# Easy_RFPA_RevA_S1.net
KiCad netlist of a schematic drawn in EAGLE
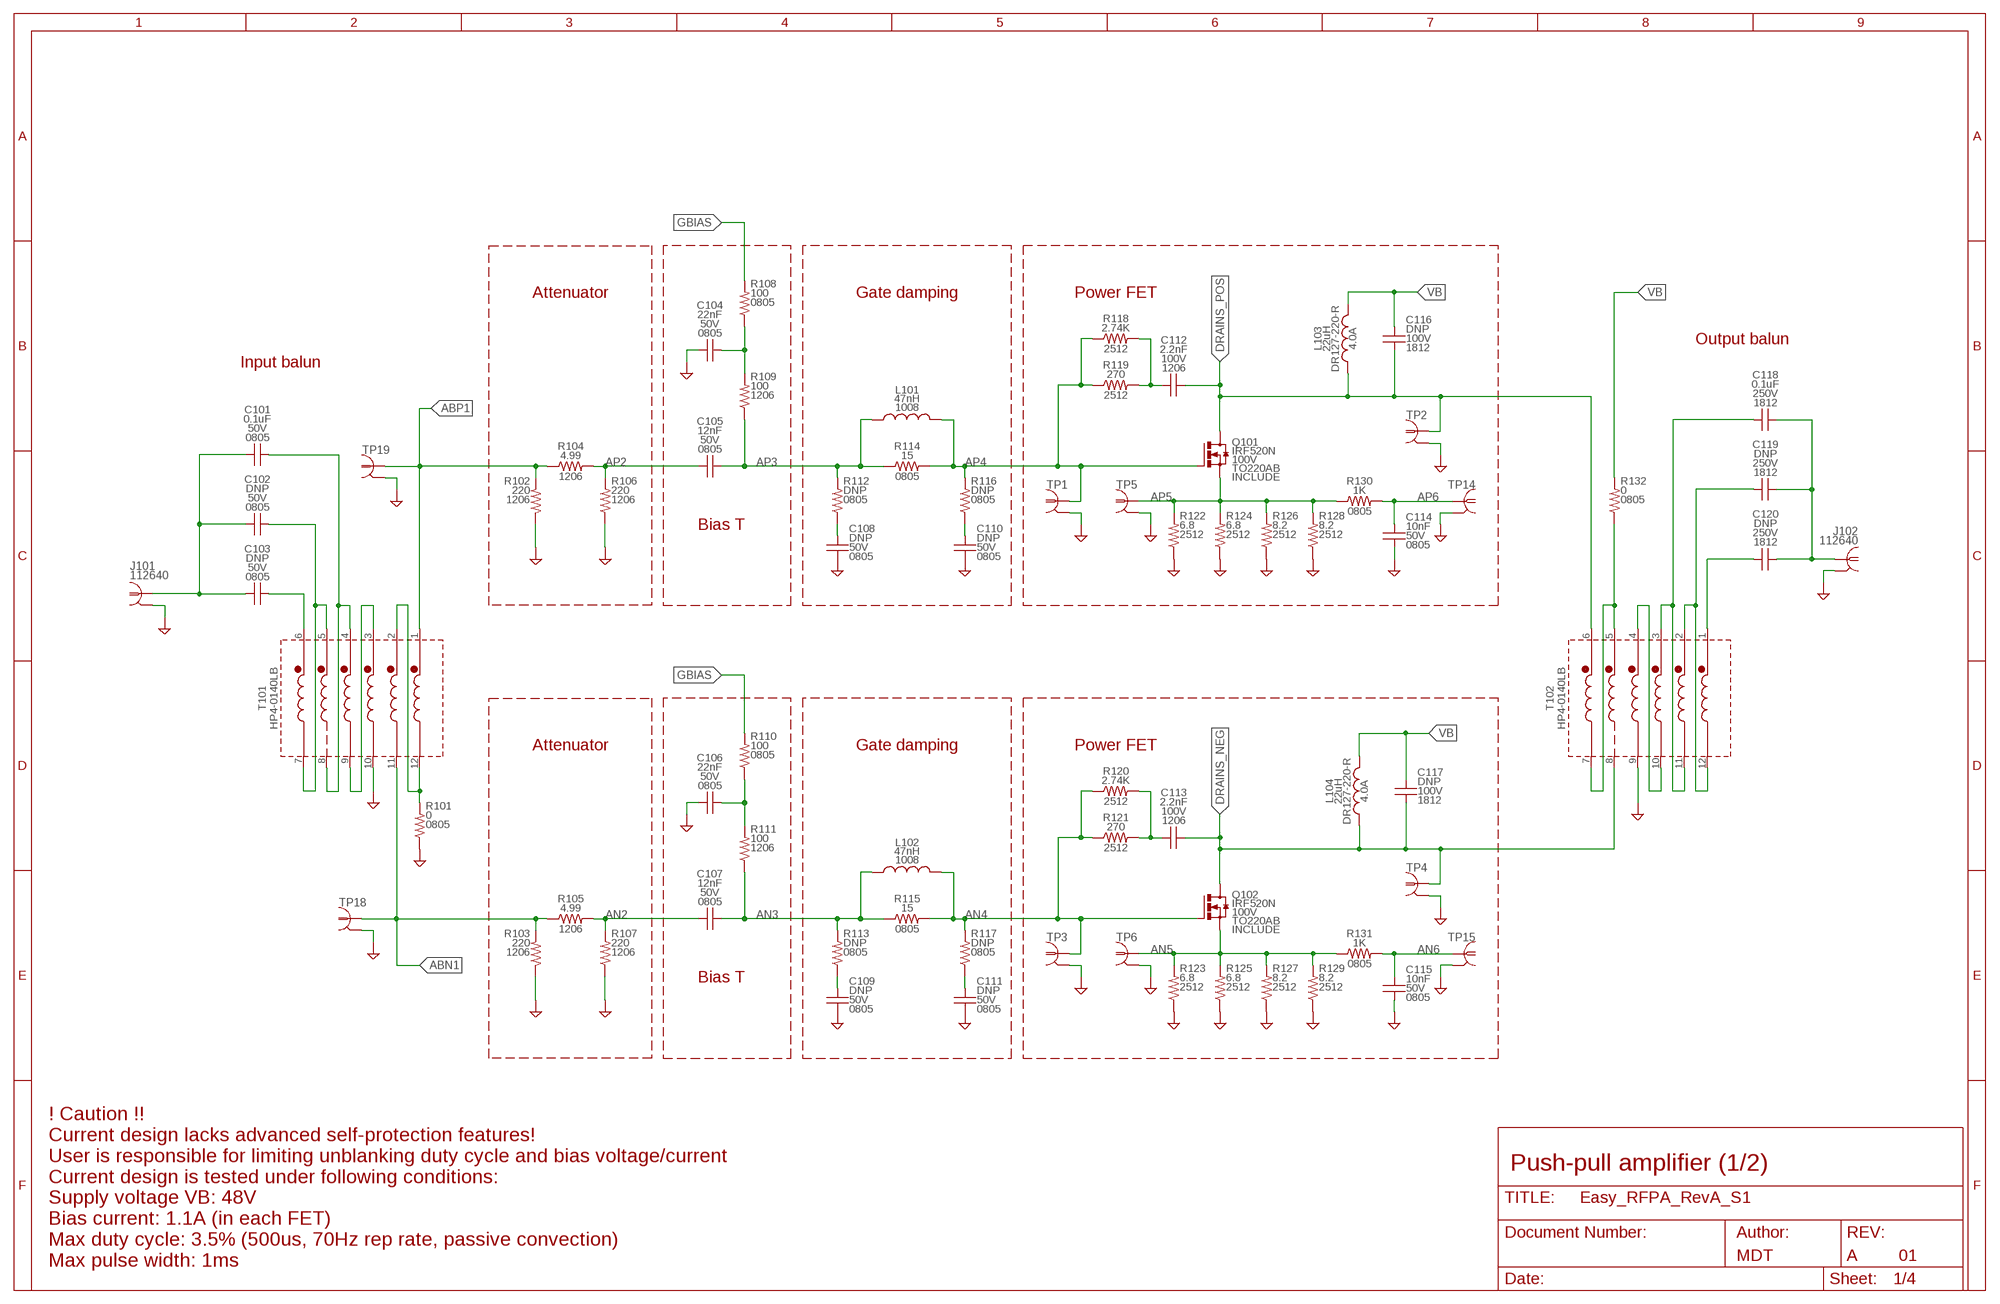
[diagram p0: schematic, sheet 1]
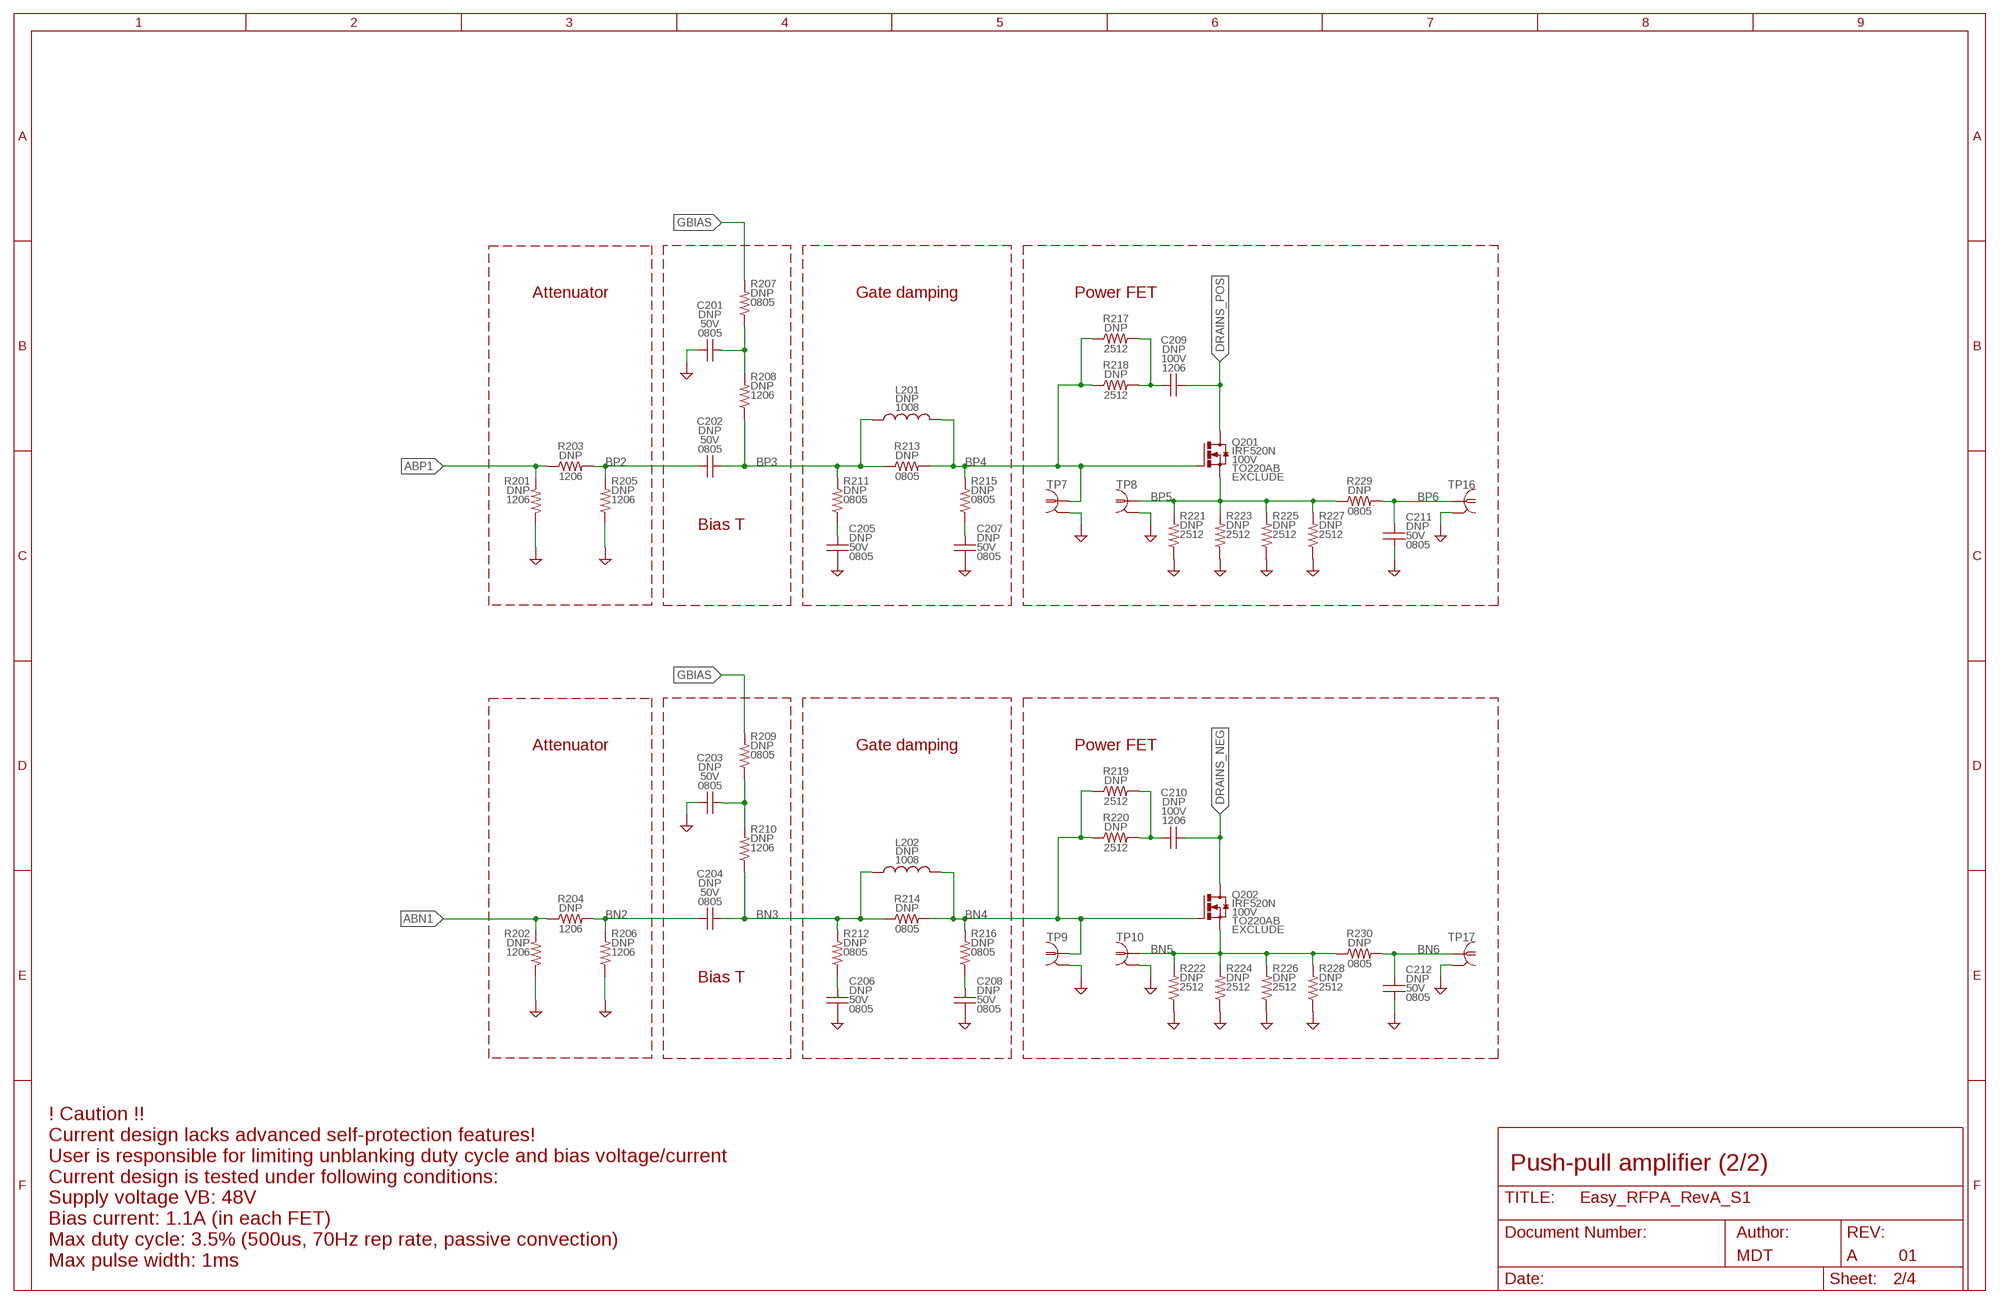
[diagram p1: schematic, sheet 2]
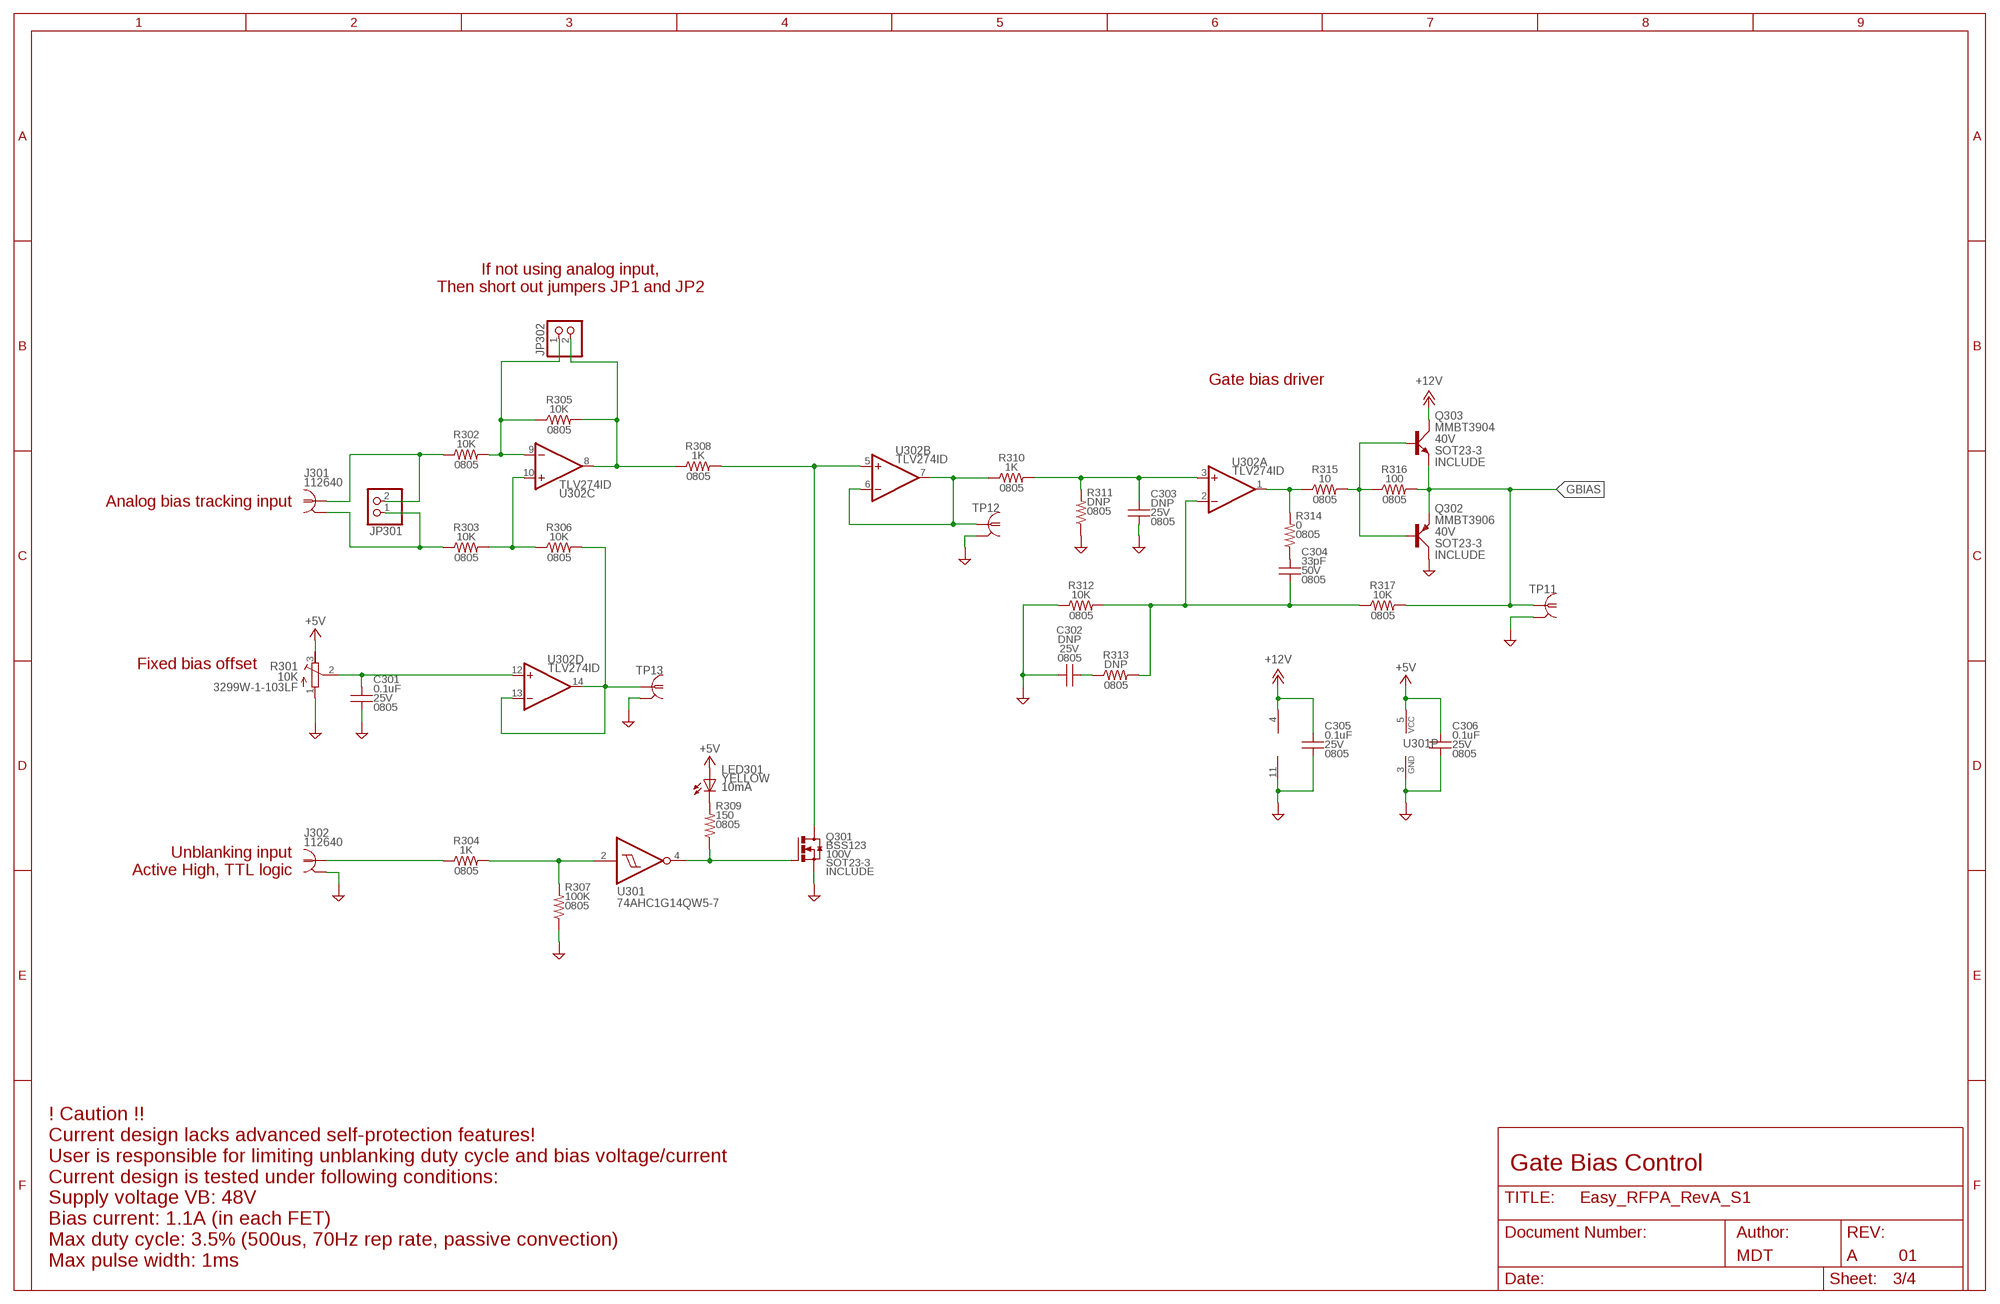
[diagram p2: schematic, sheet 3]
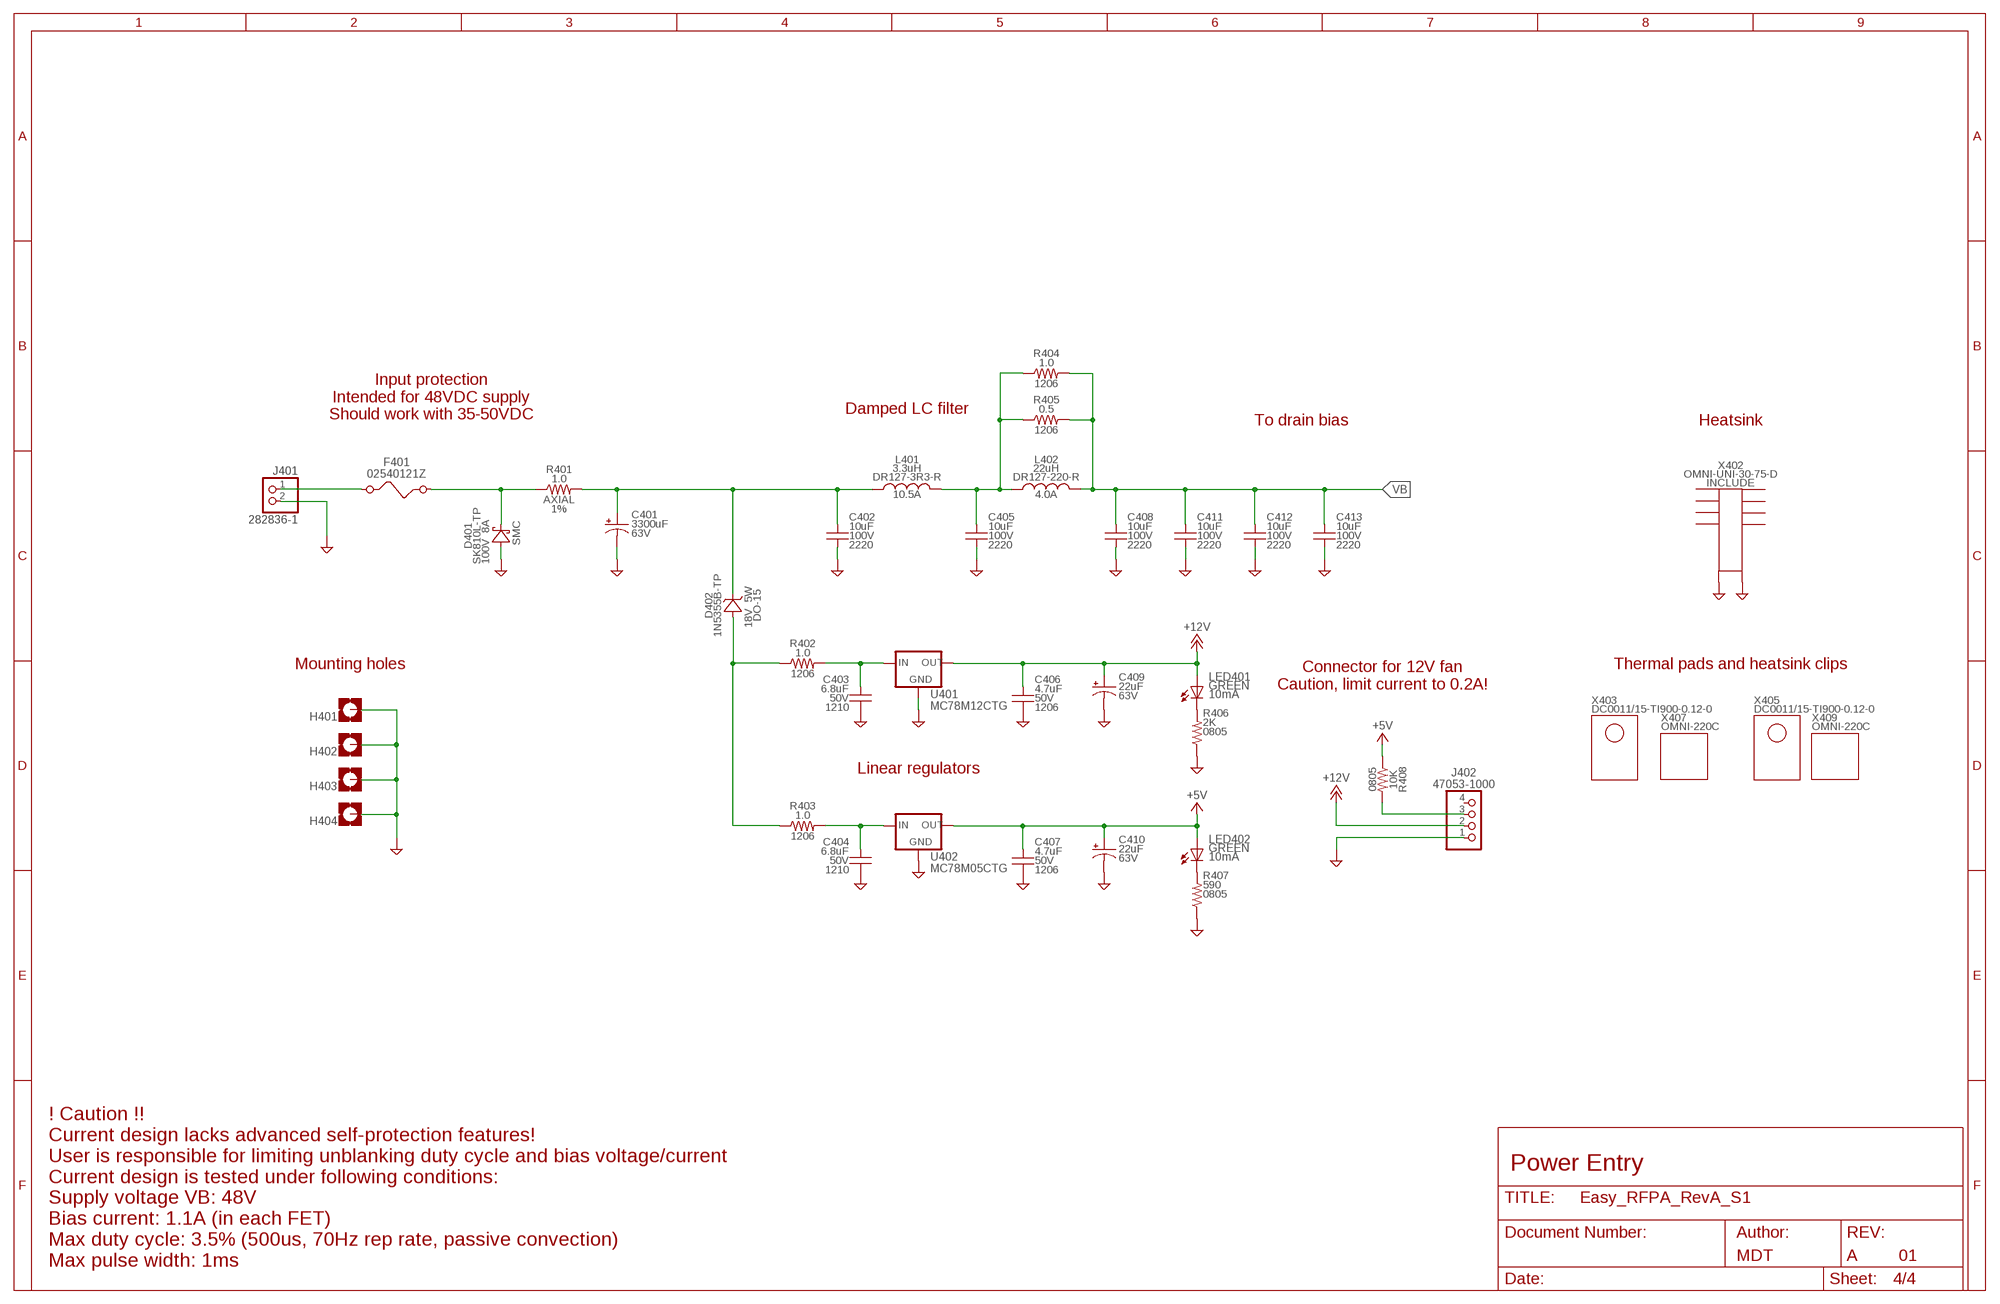
[diagram p3: schematic, sheet 4]

(export (version "E")
  (design (tool "Eeschema 10.0.6"))
  (components
    (comp (ref "C201")
      (value "DNP")
      (footprint "eagle-import:0805_IPC-7351B")
      (fields (field (name "PACKAGE") "0805") (field (name "BOM") "EXCLUDE") (field (name "VOLTAGE") "50V"))
      (libsource (lib "eagle-import") (part "C0805_IPCGEN"))
    )
    (comp (ref "C202")
      (value "DNP")
      (footprint "eagle-import:0805_IPC-7351B")
      (fields (field (name "PACKAGE") "0805") (field (name "BOM") "EXCLUDE") (field (name "VOLTAGE") "50V"))
      (libsource (lib "eagle-import") (part "C0805_IPCGEN"))
    )
    (comp (ref "C203")
      (value "DNP")
      (footprint "eagle-import:0805_IPC-7351B")
      (fields (field (name "PACKAGE") "0805") (field (name "BOM") "EXCLUDE") (field (name "VOLTAGE") "50V"))
      (libsource (lib "eagle-import") (part "C0805_IPCGEN"))
    )
    (comp (ref "C204")
      (value "DNP")
      (footprint "eagle-import:0805_IPC-7351B")
      (fields (field (name "PACKAGE") "0805") (field (name "BOM") "EXCLUDE") (field (name "VOLTAGE") "50V"))
      (libsource (lib "eagle-import") (part "C0805_IPCGEN"))
    )
    (comp (ref "C205")
      (value "DNP")
      (footprint "eagle-import:0805_IPC-7351B")
      (fields (field (name "BOM") "EXCLUDE") (field (name "VOLTAGE") "50V"))
      (libsource (lib "eagle-import") (part "C0805_IPCGEN"))
    )
    (comp (ref "C206")
      (value "DNP")
      (footprint "eagle-import:0805_IPC-7351B")
      (fields (field (name "BOM") "EXCLUDE") (field (name "VOLTAGE") "50V"))
      (libsource (lib "eagle-import") (part "C0805_IPCGEN"))
    )
    (comp (ref "C207")
      (value "DNP")
      (footprint "eagle-import:0805_IPC-7351B")
      (fields (field (name "BOM") "EXCLUDE") (field (name "VOLTAGE") "50V"))
      (libsource (lib "eagle-import") (part "C0805_IPCGEN"))
    )
    (comp (ref "C208")
      (value "DNP")
      (footprint "eagle-import:0805_IPC-7351B")
      (fields (field (name "BOM") "EXCLUDE") (field (name "VOLTAGE") "50V"))
      (libsource (lib "eagle-import") (part "C0805_IPCGEN"))
    )
    (comp (ref "C209")
      (value "DNP")
      (footprint "eagle-import:C1206")
      (fields (field (name "PACKAGE") "1206") (field (name "BOM") "EXCLUDE") (field (name "VOLTAGE") "100V"))
      (libsource (lib "eagle-import") (part "CC1206GEN"))
    )
    (comp (ref "C210")
      (value "DNP")
      (footprint "eagle-import:C1206")
      (fields (field (name "PACKAGE") "1206") (field (name "BOM") "EXCLUDE") (field (name "VOLTAGE") "100V"))
      (libsource (lib "eagle-import") (part "CC1206GEN"))
    )
    (comp (ref "C211")
      (value "DNP")
      (footprint "eagle-import:0805_IPC-7351B")
      (fields (field (name "BOM") "EXCLUDE") (field (name "VOLTAGE") "50V"))
      (libsource (lib "eagle-import") (part "C0805_IPCGEN"))
    )
    (comp (ref "C212")
      (value "DNP")
      (footprint "eagle-import:0805_IPC-7351B")
      (fields (field (name "BOM") "EXCLUDE") (field (name "VOLTAGE") "50V"))
      (libsource (lib "eagle-import") (part "C0805_IPCGEN"))
    )
    (comp (ref "L201")
      (value "DNP")
      (footprint "eagle-import:L1008")
      (fields (field (name "PARTNO") "1008CS-470XJLC") (field (name "BOM") "EXCLUDE"))
      (libsource (lib "eagle-import") (part "L_CHIP1008L-47N-AIR-5%-1008-1A"))
    )
    (comp (ref "L202")
      (value "DNP")
      (footprint "eagle-import:L1008")
      (fields (field (name "PARTNO") "1008CS-470XJLC") (field (name "BOM") "EXCLUDE"))
      (libsource (lib "eagle-import") (part "L_CHIP1008L-47N-AIR-5%-1008-1A"))
    )
    (comp (ref "Q201")
      (value "IRF630")
      (footprint "eagle-import:TO220BV")
      (fields
        (field (name "PARTNO") "IRF520NPBF")
        (field (name "VOLTAGE") "100V")
        (field (name "BOM") "EXCLUDE")
      )
      (libsource (lib "eagle-import") (part "MOSFET_NTO-220-VERTIRF520N"))
    )
    (comp (ref "Q202")
      (value "IRF630")
      (footprint "eagle-import:TO220BV")
      (fields
        (field (name "PARTNO") "IRF520NPBF")
        (field (name "VOLTAGE") "100V")
        (field (name "BOM") "EXCLUDE")
      )
      (libsource (lib "eagle-import") (part "MOSFET_NTO-220-VERTIRF520N"))
    )
    (comp (ref "R201")
      (value "DNP")
      (footprint "eagle-import:1206_IPC-7351B")
      (fields (field (name "BOM") "EXCLUDE"))
      (libsource (lib "eagle-import") (part "R1206_IPCGEN"))
    )
    (comp (ref "R202")
      (value "DNP")
      (footprint "eagle-import:1206_IPC-7351B")
      (fields (field (name "BOM") "EXCLUDE"))
      (libsource (lib "eagle-import") (part "R1206_IPCGEN"))
    )
    (comp (ref "R203")
      (value "DNP")
      (footprint "eagle-import:1206_IPC-7351B")
      (fields (field (name "BOM") "EXCLUDE"))
      (libsource (lib "eagle-import") (part "R901206_IPCGEN"))
    )
    (comp (ref "R204")
      (value "DNP")
      (footprint "eagle-import:1206_IPC-7351B")
      (fields (field (name "BOM") "EXCLUDE"))
      (libsource (lib "eagle-import") (part "R901206_IPCGEN"))
    )
    (comp (ref "R205")
      (value "DNP")
      (footprint "eagle-import:1206_IPC-7351B")
      (fields (field (name "BOM") "EXCLUDE"))
      (libsource (lib "eagle-import") (part "R1206_IPCGEN"))
    )
    (comp (ref "R206")
      (value "DNP")
      (footprint "eagle-import:1206_IPC-7351B")
      (fields (field (name "BOM") "EXCLUDE"))
      (libsource (lib "eagle-import") (part "R1206_IPCGEN"))
    )
    (comp (ref "R207")
      (value "DNP")
      (footprint "eagle-import:0805_IPC-7351B")
      (fields (field (name "BOM") "EXCLUDE"))
      (libsource (lib "eagle-import") (part "R0805_IPCGEN"))
    )
    (comp (ref "R208")
      (value "DNP")
      (footprint "eagle-import:1206_IPC-7351B")
      (fields (field (name "BOM") "EXCLUDE"))
      (libsource (lib "eagle-import") (part "R1206_IPCGEN"))
    )
    (comp (ref "R209")
      (value "DNP")
      (footprint "eagle-import:0805_IPC-7351B")
      (fields (field (name "BOM") "EXCLUDE"))
      (libsource (lib "eagle-import") (part "R0805_IPCGEN"))
    )
    (comp (ref "R210")
      (value "DNP")
      (footprint "eagle-import:1206_IPC-7351B")
      (fields (field (name "BOM") "EXCLUDE"))
      (libsource (lib "eagle-import") (part "R1206_IPCGEN"))
    )
    (comp (ref "R211")
      (value "DNP")
      (footprint "eagle-import:0805_IPC-7351B")
      (fields (field (name "BOM") "EXCLUDE"))
      (libsource (lib "eagle-import") (part "R0805_IPCGEN"))
    )
    (comp (ref "R212")
      (value "DNP")
      (footprint "eagle-import:0805_IPC-7351B")
      (fields (field (name "BOM") "EXCLUDE"))
      (libsource (lib "eagle-import") (part "R0805_IPCGEN"))
    )
    (comp (ref "R213")
      (value "DNP")
      (footprint "eagle-import:0805_IPC-7351B")
      (fields (field (name "BOM") "EXCLUDE"))
      (libsource (lib "eagle-import") (part "R900805_IPCGEN"))
    )
    (comp (ref "R214")
      (value "DNP")
      (footprint "eagle-import:0805_IPC-7351B")
      (fields (field (name "BOM") "EXCLUDE"))
      (libsource (lib "eagle-import") (part "R900805_IPCGEN"))
    )
    (comp (ref "R215")
      (value "DNP")
      (footprint "eagle-import:0805_IPC-7351B")
      (fields (field (name "BOM") "EXCLUDE"))
      (libsource (lib "eagle-import") (part "R0805_IPCGEN"))
    )
    (comp (ref "R216")
      (value "DNP")
      (footprint "eagle-import:0805_IPC-7351B")
      (fields (field (name "BOM") "EXCLUDE"))
      (libsource (lib "eagle-import") (part "R0805_IPCGEN"))
    )
    (comp (ref "R217")
      (value "DNP")
      (footprint "eagle-import:R2512")
      (fields (field (name "BOM") "EXCLUDE"))
      (libsource (lib "eagle-import") (part "R90R2512GEN"))
    )
    (comp (ref "R218")
      (value "DNP")
      (footprint "eagle-import:R2512")
      (fields (field (name "BOM") "EXCLUDE"))
      (libsource (lib "eagle-import") (part "R90R2512GEN"))
    )
    (comp (ref "R219")
      (value "DNP")
      (footprint "eagle-import:R2512")
      (fields (field (name "BOM") "EXCLUDE"))
      (libsource (lib "eagle-import") (part "R90R2512GEN"))
    )
    (comp (ref "R220")
      (value "DNP")
      (footprint "eagle-import:R2512")
      (fields (field (name "BOM") "EXCLUDE"))
      (libsource (lib "eagle-import") (part "R90R2512GEN"))
    )
    (comp (ref "R221")
      (value "DNP")
      (footprint "eagle-import:R2512")
      (fields (field (name "BOM") "EXCLUDE"))
      (libsource (lib "eagle-import") (part "RR2512GEN"))
    )
    (comp (ref "R222")
      (value "DNP")
      (footprint "eagle-import:R2512")
      (fields (field (name "BOM") "EXCLUDE"))
      (libsource (lib "eagle-import") (part "RR2512GEN"))
    )
    (comp (ref "R223")
      (value "DNP")
      (footprint "eagle-import:R2512")
      (fields (field (name "BOM") "EXCLUDE"))
      (libsource (lib "eagle-import") (part "RR2512GEN"))
    )
    (comp (ref "R224")
      (value "DNP")
      (footprint "eagle-import:R2512")
      (fields (field (name "BOM") "EXCLUDE"))
      (libsource (lib "eagle-import") (part "RR2512GEN"))
    )
    (comp (ref "R225")
      (value "DNP")
      (footprint "eagle-import:R2512")
      (fields (field (name "BOM") "EXCLUDE"))
      (libsource (lib "eagle-import") (part "RR2512GEN"))
    )
    (comp (ref "R226")
      (value "DNP")
      (footprint "eagle-import:R2512")
      (fields (field (name "BOM") "EXCLUDE"))
      (libsource (lib "eagle-import") (part "RR2512GEN"))
    )
    (comp (ref "R227")
      (value "DNP")
      (footprint "eagle-import:R2512")
      (fields (field (name "BOM") "EXCLUDE"))
      (libsource (lib "eagle-import") (part "RR2512GEN"))
    )
    (comp (ref "R228")
      (value "DNP")
      (footprint "eagle-import:R2512")
      (fields (field (name "BOM") "EXCLUDE"))
      (libsource (lib "eagle-import") (part "RR2512GEN"))
    )
    (comp (ref "R229")
      (value "DNP")
      (footprint "eagle-import:0805_IPC-7351B")
      (fields (field (name "BOM") "EXCLUDE"))
      (libsource (lib "eagle-import") (part "R900805_IPCGEN"))
    )
    (comp (ref "R230")
      (value "DNP")
      (footprint "eagle-import:0805_IPC-7351B")
      (fields (field (name "BOM") "EXCLUDE"))
      (libsource (lib "eagle-import") (part "R900805_IPCGEN"))
    )
    (comp (ref "TP7")
      (value "PROBE_TPTP_5MM")
      (footprint "eagle-import:PROBE_TP_5MM")
      (libsource (lib "eagle-import") (part "PROBE_TPTP_5MM"))
    )
    (comp (ref "TP8")
      (value "PROBE_TPTP_7P5MM")
      (footprint "eagle-import:PROBE_TP_7P5MM")
      (libsource (lib "eagle-import") (part "PROBE_TPTP_7P5MM"))
    )
    (comp (ref "TP9")
      (value "PROBE_TPTP_5MM")
      (footprint "eagle-import:PROBE_TP_5MM")
      (libsource (lib "eagle-import") (part "PROBE_TPTP_5MM"))
    )
    (comp (ref "TP10")
      (value "PROBE_TPTP_5MM")
      (footprint "eagle-import:PROBE_TP_5MM")
      (libsource (lib "eagle-import") (part "PROBE_TPTP_5MM"))
    )
    (comp (ref "TP16")
      (value "PROBE_TPTP_5MM")
      (footprint "eagle-import:PROBE_TP_5MM")
      (libsource (lib "eagle-import") (part "PROBE_TPTP_5MM"))
    )
    (comp (ref "TP17")
      (value "PROBE_TPTP_7P5MM")
      (footprint "eagle-import:PROBE_TP_7P5MM")
      (libsource (lib "eagle-import") (part "PROBE_TPTP_7P5MM"))
    )
    (comp (ref "C401")
      (value "3300uF")
      (footprint "eagle-import:EB25D")
      (fields (field (name "PARTNO") "MAL225638332E3") (field (name "VOLTAGE") "63V"))
      (libsource (lib "eagle-import") (part "CPOLEB25DC-3300U-63V-20%-25DX37L-ELEC"))
    )
    (comp (ref "C402")
      (value "10uF")
      (footprint "eagle-import:C2220_CKG57N")
      (fields
        (field (name "BOM") "INCLUDE")
        (field (name "PACKAGE") "2220")
        (field (name "PARTNO") "CGA9N3X7S2A106M230KE")
        (field (name "VOLTAGE") "100V")
      )
      (libsource (lib "eagle-import") (part "CC2220_CKG57NCC-10U-100V-20%-2220-X7T"))
    )
    (comp (ref "C403")
      (value "6.8uF")
      (footprint "eagle-import:C1210")
      (fields (field (name "DIALECTRIC") "X7S") (field (name "VOLTAGE") "50V"))
      (libsource (lib "eagle-import") (part "CC1210GEN"))
    )
    (comp (ref "C404")
      (value "6.8uF")
      (footprint "eagle-import:C1210")
      (fields (field (name "DIALECTRIC") "X7S") (field (name "VOLTAGE") "50V"))
      (libsource (lib "eagle-import") (part "CC1210GEN"))
    )
    (comp (ref "C405")
      (value "10uF")
      (footprint "eagle-import:C2220_CKG57N")
      (fields
        (field (name "BOM") "INCLUDE")
        (field (name "PACKAGE") "2220")
        (field (name "PARTNO") "CGA9N3X7S2A106M230KE")
        (field (name "VOLTAGE") "100V")
      )
      (libsource (lib "eagle-import") (part "CC2220_CKG57NCC-10U-100V-20%-2220-X7T"))
    )
    (comp (ref "C406")
      (value "4.7uF")
      (footprint "eagle-import:C1206")
      (fields (field (name "DIALECTRIC") "X7R") (field (name "VOLTAGE") "50V"))
      (libsource (lib "eagle-import") (part "CC1206GEN"))
    )
    (comp (ref "C407")
      (value "4.7uF")
      (footprint "eagle-import:C1206")
      (fields (field (name "DIALECTRIC") "X7R") (field (name "VOLTAGE") "50V"))
      (libsource (lib "eagle-import") (part "CC1206GEN"))
    )
    (comp (ref "C408")
      (value "10uF")
      (footprint "eagle-import:C2220_CKG57N")
      (fields (field (name "PARTNO") "CGA9N3X7S2A106M230KE") (field (name "VOLTAGE") "100V"))
      (libsource (lib "eagle-import") (part "CC2220_CKG57NCC-10U-100V-20%-2220-X7T"))
    )
    (comp (ref "C409")
      (value "22uF")
      (footprint "eagle-import:E2,5-7")
      (fields (field (name "PARTNO") "860010773010") (field (name "VOLTAGE") "63V"))
      (libsource (lib "eagle-import") (part "CPOLE2,5-7C-22U-63V-20%-6.3DX12.5L-ELEC"))
    )
    (comp (ref "C410")
      (value "22uF")
      (footprint "eagle-import:E2,5-7")
      (fields (field (name "PARTNO") "860010773010") (field (name "VOLTAGE") "63V"))
      (libsource (lib "eagle-import") (part "CPOLE2,5-7C-22U-63V-20%-6.3DX12.5L-ELEC"))
    )
    (comp (ref "C411")
      (value "10uF")
      (footprint "eagle-import:C2220_CKG57N")
      (fields (field (name "PARTNO") "CGA9N3X7S2A106M230KE") (field (name "VOLTAGE") "100V"))
      (libsource (lib "eagle-import") (part "CC2220_CKG57NCC-10U-100V-20%-2220-X7T"))
    )
    (comp (ref "C412")
      (value "10uF")
      (footprint "eagle-import:C2220_CKG57N")
      (fields (field (name "PARTNO") "CGA9N3X7S2A106M230KE") (field (name "VOLTAGE") "100V"))
      (libsource (lib "eagle-import") (part "CC2220_CKG57NCC-10U-100V-20%-2220-X7T"))
    )
    (comp (ref "C413")
      (value "10uF")
      (footprint "eagle-import:C2220_CKG57N")
      (fields (field (name "PARTNO") "CGA9N3X7S2A106M230KE") (field (name "VOLTAGE") "100V"))
      (libsource (lib "eagle-import") (part "CC2220_CKG57NCC-10U-100V-20%-2220-X7T"))
    )
    (comp (ref "D401")
      (value "D-SCHOTTKYSK810L-TPSMC")
      (footprint "eagle-import:DO-214AB(SMC)")
      (fields (field (name "PARTNO") "SK810L-TP") (field (name "VOLTAGE") "100V"))
      (libsource (lib "eagle-import") (part "D-SCHOTTKYSMCSK810L-TP"))
    )
    (comp (ref "D402")
      (value "D-ZENER1N5355B-TPDO15-12")
      (footprint "eagle-import:DO15-12")
      (fields (field (name "PARTNO") "1N5355B-TP") (field (name "POWER") "5W") (field (name "VOLTAGE") "18V"))
      (libsource (lib "eagle-import") (part "D-ZENERDO15-121N5355B-TP"))
    )
    (comp (ref "F401")
      (value "FUSE_2P")
      (footprint "eagle-import:02540121Z")
      (fields (field (name "PARTNO") "02540121Z"))
      (libsource (lib "eagle-import") (part "FUSE_2P"))
    )
    (comp (ref "H401")
      (value "MOUNT-PAD-SQUARE3.2")
      (footprint "eagle-import:3,2-PAD-SQUARE")
      (libsource (lib "eagle-import") (part "MOUNT-PAD-SQUARE3.2"))
    )
    (comp (ref "H402")
      (value "MOUNT-PAD-SQUARE3.2")
      (footprint "eagle-import:3,2-PAD-SQUARE")
      (libsource (lib "eagle-import") (part "MOUNT-PAD-SQUARE3.2"))
    )
    (comp (ref "H403")
      (value "MOUNT-PAD-SQUARE3.2")
      (footprint "eagle-import:3,2-PAD-SQUARE")
      (libsource (lib "eagle-import") (part "MOUNT-PAD-SQUARE3.2"))
    )
    (comp (ref "H404")
      (value "MOUNT-PAD-SQUARE3.2")
      (footprint "eagle-import:3,2-PAD-SQUARE")
      (libsource (lib "eagle-import") (part "MOUNT-PAD-SQUARE3.2"))
    )
    (comp (ref "J401")
      (value "HDR_2X1282836-1282836-1")
      (footprint "eagle-import:W237-02")
      (fields (field (name "PARTNO") "282836-1"))
      (libsource (lib "eagle-import") (part "HDR_2X1282836-1282836-1"))
    )
    (comp (ref "J402")
      (value "KK_PCFAN")
      (footprint "eagle-import:47053-1000")
      (fields (field (name "PARTNO") "47053-1000"))
      (libsource (lib "eagle-import") (part "KK_PCFAN"))
    )
    (comp (ref "L401")
      (value "3.3uH")
      (footprint "eagle-import:DR127")
      (fields (field (name "PARTNO") "DR127-3R3-R"))
      (libsource (lib "eagle-import") (part "LL-3.3U-FERRITE-20%-12.5X12.5MM-10.5A"))
    )
    (comp (ref "L402")
      (value "22uH")
      (footprint "eagle-import:DR127")
      (fields (field (name "PARTNO") "DR127-220-R"))
      (libsource (lib "eagle-import") (part "LL-22U-FERRITE-20%-12.5X12.5MM-4A"))
    )
    (comp (ref "LED401")
      (value "LEDHLMP-3962-F0002T1_3/4")
      (footprint "eagle-import:LED5MM")
      (fields (field (name "PARTNO") "HLMP-3962-F0002"))
      (libsource (lib "eagle-import") (part "LEDT1_3/4HLMP-3962-F0002"))
    )
    (comp (ref "LED402")
      (value "LEDHLMP-3962-F0002T1_3/4")
      (footprint "eagle-import:LED5MM")
      (fields (field (name "PARTNO") "HLMP-3962-F0002"))
      (libsource (lib "eagle-import") (part "LEDT1_3/4HLMP-3962-F0002"))
    )
    (comp (ref "R401")
      (value "1.0")
      (footprint "eagle-import:P0817V")
      (fields (field (name "PARTNO") "PAC300001008FAC000") (field (name "POWER") "3W"))
      (libsource (lib "eagle-import") (part "R90P0817VR-1.0-1%-AXIAL-3W"))
    )
    (comp (ref "R402")
      (value "1.0")
      (footprint "eagle-import:R1206")
      (libsource (lib "eagle-import") (part "R90R1206GEN"))
    )
    (comp (ref "R403")
      (value "1.0")
      (footprint "eagle-import:R1206")
      (libsource (lib "eagle-import") (part "R90R1206GEN"))
    )
    (comp (ref "R404")
      (value "1.0")
      (footprint "eagle-import:1206_IPC-7351B")
      (libsource (lib "eagle-import") (part "R901206_IPCGEN"))
    )
    (comp (ref "R405")
      (value "0.5")
      (footprint "eagle-import:1206_IPC-7351B")
      (libsource (lib "eagle-import") (part "R901206_IPCGEN"))
    )
    (comp (ref "R406")
      (value "2K")
      (footprint "eagle-import:0805_IPC-7351B")
      (libsource (lib "eagle-import") (part "R0805_IPCGEN"))
    )
    (comp (ref "R407")
      (value "590")
      (footprint "eagle-import:0805_IPC-7351B")
      (libsource (lib "eagle-import") (part "R0805_IPCGEN"))
    )
    (comp (ref "R408")
      (value "10K")
      (footprint "eagle-import:0805_IPC-7351B")
      (libsource (lib "eagle-import") (part "R900805_IPCGEN"))
    )
    (comp (ref "U401")
      (value "LDO_3TERMMC78M12CTGTO220_VERT")
      (footprint "eagle-import:TO220BV")
      (fields (field (name "PARTNO") "MC78M12CTG"))
      (libsource (lib "eagle-import") (part "LDO_3TERMTO220_VERTMC78M12CTG"))
    )
    (comp (ref "U402")
      (value "LDO_3TERMMC78M05CTGTO220_VERT")
      (footprint "eagle-import:TO220BV")
      (fields (field (name "PARTNO") "MC78M05CTG"))
      (libsource (lib "eagle-import") (part "LDO_3TERMTO220_VERTMC78M05CTG"))
    )
    (comp (ref "X402")
      (value "HEATSINK_OMNI_DUALOMNI-UNI-30-75-D30-75-D")
      (footprint "eagle-import:OMNI-UNI-30-75-D")
      (fields (field (name "PARTNO") "OMNI-UNI-30-75-D"))
      (libsource (lib "eagle-import") (part "HEATSINK_OMNI_DUAL30-75-DOMNI-UNI-30-75-D"))
    )
    (comp (ref "C301")
      (value "0.1uF")
      (footprint "eagle-import:0805_IPC-7351B")
      (fields (field (name "VOLTAGE") "25V"))
      (libsource (lib "eagle-import") (part "C0805_IPCGEN"))
    )
    (comp (ref "C302")
      (value "DNP")
      (footprint "eagle-import:0805_IPC-7351B")
      (fields (field (name "PACKAGE") "0805") (field (name "BOM") "EXCLUDE") (field (name "VOLTAGE") "25V"))
      (libsource (lib "eagle-import") (part "C0805_IPCGEN"))
    )
    (comp (ref "C303")
      (value "DNP")
      (footprint "eagle-import:0805_IPC-7351B")
      (fields (field (name "BOM") "EXCLUDE") (field (name "VOLTAGE") "25V"))
      (libsource (lib "eagle-import") (part "C0805_IPCGEN"))
    )
    (comp (ref "C304")
      (value "33pF")
      (footprint "eagle-import:0805_IPC-7351B")
      (fields (field (name "VOLTAGE") "50V"))
      (libsource (lib "eagle-import") (part "C0805_IPCGEN"))
    )
    (comp (ref "C305")
      (value "0.1uF")
      (footprint "eagle-import:0805_IPC-7351B")
      (fields (field (name "VOLTAGE") "25V"))
      (libsource (lib "eagle-import") (part "C0805_IPCGEN"))
    )
    (comp (ref "C306")
      (value "0.1uF")
      (footprint "eagle-import:0805_IPC-7351B")
      (fields (field (name "VOLTAGE") "25V"))
      (libsource (lib "eagle-import") (part "C0805_IPCGEN"))
    )
    (comp (ref "J301")
      (value "COAX112640BNC_EDGE")
      (footprint "eagle-import:BNC_EDGE")
      (fields (field (name "PARTNO") "112640"))
      (libsource (lib "eagle-import") (part "COAXBNC_EDGE112640"))
    )
    (comp (ref "J302")
      (value "COAX112640BNC_EDGE")
      (footprint "eagle-import:BNC_EDGE")
      (fields (field (name "PARTNO") "112640"))
      (libsource (lib "eagle-import") (part "COAXBNC_EDGE112640"))
    )
    (comp (ref "JP301")
      (value "PINHD-1X2")
      (footprint "eagle-import:1X02")
      (libsource (lib "eagle-import") (part "PINHD-1X2"))
    )
    (comp (ref "JP302")
      (value "PINHD-1X2")
      (footprint "eagle-import:1X02")
      (libsource (lib "eagle-import") (part "PINHD-1X2"))
    )
    (comp (ref "LED301")
      (value "LEDHLMP-3401-E0002T1_3/4")
      (footprint "eagle-import:LED5MM")
      (fields (field (name "PARTNO") " HLMP-3401-E0002"))
      (libsource (lib "eagle-import") (part "LEDT1_3/4HLMP-3401-E0002"))
    )
    (comp (ref "Q301")
      (value "MOSFET_NBSS123SOT23")
      (footprint "eagle-import:SOT23R_INFINEON")
      (fields (field (name "PARTNO") "BSS123-7-F") (field (name "VOLTAGE") "100V"))
      (libsource (lib "eagle-import") (part "MOSFET_NSOT23BSS123"))
    )
    (comp (ref "Q302")
      (value "PNPSOT23_BEC")
      (footprint "eagle-import:SOT23R_INFINEON")
      (fields (field (name "VOLTAGE") "40V") (field (name "PARTNO") "PMBT3906,215"))
      (libsource (lib "eagle-import") (part "PNPSOT23_BEC"))
    )
    (comp (ref "Q303")
      (value "NPNMMBT3904SOT23_BEC")
      (footprint "eagle-import:SOT23R_INFINEON")
      (fields (field (name "PARTNO") "MMBT3904,215") (field (name "VOLTAGE") "40V"))
      (libsource (lib "eagle-import") (part "NPNSOT23_BECMMBT3904"))
    )
    (comp (ref "R301")
      (value "10K")
      (footprint "eagle-import:RTRIM3299W")
      (fields (field (name "PARTNO") "3299W-1-103LF") (field (name "POWER") "0.5W"))
      (libsource (lib "eagle-import") (part "RTRIM3299WRTRIM-10K-10%-3299W-0.5W"))
    )
    (comp (ref "R302")
      (value "10K")
      (footprint "eagle-import:0805_IPC-7351B")
      (libsource (lib "eagle-import") (part "R900805_IPCGEN"))
    )
    (comp (ref "R303")
      (value "10K")
      (footprint "eagle-import:0805_IPC-7351B")
      (libsource (lib "eagle-import") (part "R900805_IPCGEN"))
    )
    (comp (ref "R304")
      (value "1K")
      (footprint "eagle-import:0805_IPC-7351B")
      (libsource (lib "eagle-import") (part "R900805_IPCGEN"))
    )
    (comp (ref "R305")
      (value "10K")
      (footprint "eagle-import:0805_IPC-7351B")
      (libsource (lib "eagle-import") (part "R900805_IPCGEN"))
    )
    (comp (ref "R306")
      (value "10K")
      (footprint "eagle-import:0805_IPC-7351B")
      (libsource (lib "eagle-import") (part "R900805_IPCGEN"))
    )
    (comp (ref "R307")
      (value "100K")
      (footprint "eagle-import:0805_IPC-7351B")
      (libsource (lib "eagle-import") (part "R0805_IPCGEN"))
    )
    (comp (ref "R308")
      (value "1K")
      (footprint "eagle-import:0805_IPC-7351B")
      (libsource (lib "eagle-import") (part "R900805_IPCGEN"))
    )
    (comp (ref "R309")
      (value "150")
      (footprint "eagle-import:0805_IPC-7351B")
      (libsource (lib "eagle-import") (part "R0805_IPCGEN"))
    )
    (comp (ref "R310")
      (value "1K")
      (footprint "eagle-import:0805_IPC-7351B")
      (libsource (lib "eagle-import") (part "R900805_IPCGEN"))
    )
    (comp (ref "R311")
      (value "DNP")
      (footprint "eagle-import:0805_IPC-7351B")
      (fields (field (name "BOM") "EXCLUDE"))
      (libsource (lib "eagle-import") (part "R0805_IPCGEN"))
    )
    (comp (ref "R312")
      (value "10K")
      (footprint "eagle-import:0805_IPC-7351B")
      (libsource (lib "eagle-import") (part "R900805_IPCGEN"))
    )
    (comp (ref "R313")
      (value "DNP")
      (footprint "eagle-import:0805_IPC-7351B")
      (fields (field (name "BOM") "EXCLUDE"))
      (libsource (lib "eagle-import") (part "R900805_IPCGEN"))
    )
    (comp (ref "R314")
      (value "0")
      (footprint "eagle-import:0805_IPC-7351B")
      (libsource (lib "eagle-import") (part "R0805_IPCGEN"))
    )
    (comp (ref "R315")
      (value "10")
      (footprint "eagle-import:0805_IPC-7351B")
      (libsource (lib "eagle-import") (part "R900805_IPCGEN"))
    )
    (comp (ref "R316")
      (value "100")
      (footprint "eagle-import:0805_IPC-7351B")
      (libsource (lib "eagle-import") (part "R900805_IPCGEN"))
    )
    (comp (ref "R317")
      (value "10K")
      (footprint "eagle-import:0805_IPC-7351B")
      (libsource (lib "eagle-import") (part "R900805_IPCGEN"))
    )
    (comp (ref "TP11")
      (value "PROBE_TPTP_5MM")
      (footprint "eagle-import:PROBE_TP_5MM")
      (libsource (lib "eagle-import") (part "PROBE_TPTP_5MM"))
    )
    (comp (ref "TP12")
      (value "PROBE_TPTP_5MM")
      (footprint "eagle-import:PROBE_TP_5MM")
      (libsource (lib "eagle-import") (part "PROBE_TPTP_5MM"))
    )
    (comp (ref "TP13")
      (value "PROBE_TPTP_5MM")
      (footprint "eagle-import:PROBE_TP_5MM")
      (libsource (lib "eagle-import") (part "PROBE_TPTP_5MM"))
    )
    (comp (ref "U301")
      (value "74AHC1G14DBV")
      (footprint "eagle-import:SOT23-5")
      (description "IC INVERT SCHMITT 1CH 1-IN SOT25")
      (fields
        (field (name "PARTNO") "74AHC1G14QW5-7")
        (field (name "BOM") "INCLUDE")
        (field (name "PACKAGE") "SOT23-5")
        (field (name "VENDOR") "Diodes Inc")
      )
      (libsource (lib "eagle-import") (part "741G14DBVAHC"))
    )
    (comp (ref "U302")
      (value "OPAMP_QUADTLV274IDSOIC14")
      (footprint "eagle-import:SO14")
      (fields (field (name "PARTNO") "TLV274ID"))
      (libsource (lib "eagle-import") (part "OPAMP_QUADSOIC14TLV274ID"))
    )
    (comp (ref "C101")
      (value "0.1uF")
      (footprint "eagle-import:0805_IPC-7351B")
      (fields (field (name "PACKAGE") "0805") (field (name "VOLTAGE") "50V"))
      (libsource (lib "eagle-import") (part "C0805_IPCGEN"))
    )
    (comp (ref "C102")
      (value "DNP")
      (footprint "eagle-import:0805_IPC-7351B")
      (fields (field (name "PACKAGE") "0805") (field (name "BOM") "EXCLUDE") (field (name "VOLTAGE") "50V"))
      (libsource (lib "eagle-import") (part "C0805_IPCGEN"))
    )
    (comp (ref "C103")
      (value "DNP")
      (footprint "eagle-import:0805_IPC-7351B")
      (fields (field (name "PACKAGE") "0805") (field (name "BOM") "EXCLUDE") (field (name "VOLTAGE") "50V"))
      (libsource (lib "eagle-import") (part "C0805_IPCGEN"))
    )
    (comp (ref "C104")
      (value "22nF")
      (footprint "eagle-import:0805_IPC-7351B")
      (fields (field (name "BOM") "INCLUDE") (field (name "PACKAGE") "0805") (field (name "VOLTAGE") "50V"))
      (libsource (lib "eagle-import") (part "C0805_IPCGEN"))
    )
    (comp (ref "C105")
      (value "12nF")
      (footprint "eagle-import:0805_IPC-7351B")
      (fields (field (name "PACKAGE") "0805") (field (name "VOLTAGE") "50V"))
      (libsource (lib "eagle-import") (part "C0805_IPCGEN"))
    )
    (comp (ref "C106")
      (value "22nF")
      (footprint "eagle-import:0805_IPC-7351B")
      (fields (field (name "PACKAGE") "0805") (field (name "VOLTAGE") "50V"))
      (libsource (lib "eagle-import") (part "C0805_IPCGEN"))
    )
    (comp (ref "C107")
      (value "12nF")
      (footprint "eagle-import:0805_IPC-7351B")
      (fields (field (name "PACKAGE") "0805") (field (name "VOLTAGE") "50V"))
      (libsource (lib "eagle-import") (part "C0805_IPCGEN"))
    )
    (comp (ref "C108")
      (value "DNP")
      (footprint "eagle-import:0805_IPC-7351B")
      (fields (field (name "BOM") "EXCLUDE") (field (name "VOLTAGE") "50V"))
      (libsource (lib "eagle-import") (part "C0805_IPCGEN"))
    )
    (comp (ref "C109")
      (value "DNP")
      (footprint "eagle-import:0805_IPC-7351B")
      (fields (field (name "BOM") "EXCLUDE") (field (name "VOLTAGE") "50V"))
      (libsource (lib "eagle-import") (part "C0805_IPCGEN"))
    )
    (comp (ref "C110")
      (value "DNP")
      (footprint "eagle-import:0805_IPC-7351B")
      (fields (field (name "BOM") "EXCLUDE") (field (name "VOLTAGE") "50V"))
      (libsource (lib "eagle-import") (part "C0805_IPCGEN"))
    )
    (comp (ref "C111")
      (value "DNP")
      (footprint "eagle-import:0805_IPC-7351B")
      (fields (field (name "BOM") "EXCLUDE") (field (name "VOLTAGE") "50V"))
      (libsource (lib "eagle-import") (part "C0805_IPCGEN"))
    )
    (comp (ref "C112")
      (value "2.2nF")
      (footprint "eagle-import:C1206")
      (fields (field (name "PACKAGE") "1206") (field (name "VOLTAGE") "100V"))
      (libsource (lib "eagle-import") (part "CC1206GEN"))
    )
    (comp (ref "C113")
      (value "2.2nF")
      (footprint "eagle-import:C1206")
      (fields (field (name "PACKAGE") "1206") (field (name "VOLTAGE") "100V"))
      (libsource (lib "eagle-import") (part "CC1206GEN"))
    )
    (comp (ref "C114")
      (value "10nF")
      (footprint "eagle-import:0805_IPC-7351B")
      (fields (field (name "VOLTAGE") "50V"))
      (libsource (lib "eagle-import") (part "C0805_IPCGEN"))
    )
    (comp (ref "C115")
      (value "10nF")
      (footprint "eagle-import:0805_IPC-7351B")
      (fields (field (name "VOLTAGE") "50V"))
      (libsource (lib "eagle-import") (part "C0805_IPCGEN"))
    )
    (comp (ref "C116")
      (value "DNP")
      (footprint "eagle-import:C1812")
      (fields (field (name "BOM") "EXCLUDE") (field (name "VOLTAGE") "100V"))
      (libsource (lib "eagle-import") (part "CC1812GEN"))
    )
    (comp (ref "C117")
      (value "DNP")
      (footprint "eagle-import:C1812")
      (fields (field (name "BOM") "EXCLUDE") (field (name "VOLTAGE") "100V"))
      (libsource (lib "eagle-import") (part "CC1812GEN"))
    )
    (comp (ref "C118")
      (value "0.1uF")
      (footprint "eagle-import:C1812")
      (fields (field (name "PACKAGE") "1812") (field (name "VOLTAGE") "250V"))
      (libsource (lib "eagle-import") (part "CC1812GEN"))
    )
    (comp (ref "C119")
      (value "DNP")
      (footprint "eagle-import:C1812")
      (fields (field (name "PACKAGE") "1812") (field (name "BOM") "EXCLUDE") (field (name "VOLTAGE") "250V"))
      (libsource (lib "eagle-import") (part "CC1812GEN"))
    )
    (comp (ref "C120")
      (value "DNP")
      (footprint "eagle-import:C1812")
      (fields (field (name "PACKAGE") "1812") (field (name "BOM") "EXCLUDE") (field (name "VOLTAGE") "250V"))
      (libsource (lib "eagle-import") (part "CC1812GEN"))
    )
    (comp (ref "J101")
      (value "COAX112640BNC_EDGE")
      (footprint "eagle-import:BNC_EDGE")
      (fields (field (name "PARTNO") "112640"))
      (libsource (lib "eagle-import") (part "COAXBNC_EDGE112640"))
    )
    (comp (ref "J102")
      (value "COAX112640BNC_EDGE")
      (footprint "eagle-import:BNC_EDGE")
      (fields (field (name "PARTNO") "112640"))
      (libsource (lib "eagle-import") (part "COAXBNC_EDGE112640"))
    )
    (comp (ref "L101")
      (value "47nH")
      (footprint "eagle-import:L1008")
      (fields (field (name "PARTNO") "1008CS-470XJLC"))
      (libsource (lib "eagle-import") (part "L_CHIP1008L-47N-AIR-5%-1008-1A"))
    )
    (comp (ref "L102")
      (value "47nH")
      (footprint "eagle-import:L1008")
      (fields (field (name "PARTNO") "1008CS-470XJLC"))
      (libsource (lib "eagle-import") (part "L_CHIP1008L-47N-AIR-5%-1008-1A"))
    )
    (comp (ref "L103")
      (value "22uH")
      (footprint "eagle-import:DR127")
      (fields (field (name "PARTNO") "DR127-220-R"))
      (libsource (lib "eagle-import") (part "LL-22U-FERRITE-20%-12.5X12.5MM-4A"))
    )
    (comp (ref "L104")
      (value "22uH")
      (footprint "eagle-import:DR127")
      (fields (field (name "PARTNO") "DR127-220-R"))
      (libsource (lib "eagle-import") (part "LL-22U-FERRITE-20%-12.5X12.5MM-4A"))
    )
    (comp (ref "Q101")
      (value "IRF520N")
      (footprint "eagle-import:TO220BV")
      (fields (field (name "PARTNO") "IRF520NPBF") (field (name "VOLTAGE") "100V"))
      (libsource (lib "eagle-import") (part "MOSFET_NTO-220-VERTIRF520N"))
    )
    (comp (ref "Q102")
      (value "IRF520N")
      (footprint "eagle-import:TO220BV")
      (fields (field (name "PARTNO") "IRF520NPBF") (field (name "VOLTAGE") "100V"))
      (libsource (lib "eagle-import") (part "MOSFET_NTO-220-VERTIRF520N"))
    )
    (comp (ref "R101")
      (value "0")
      (footprint "eagle-import:0805_IPC-7351B")
      (libsource (lib "eagle-import") (part "R0805_IPCGEN"))
    )
    (comp (ref "R102")
      (value "220")
      (footprint "eagle-import:1206_IPC-7351B")
      (libsource (lib "eagle-import") (part "R1206_IPCGEN"))
    )
    (comp (ref "R103")
      (value "220")
      (footprint "eagle-import:1206_IPC-7351B")
      (libsource (lib "eagle-import") (part "R1206_IPCGEN"))
    )
    (comp (ref "R104")
      (value "4.99")
      (footprint "eagle-import:1206_IPC-7351B")
      (libsource (lib "eagle-import") (part "R901206_IPCGEN"))
    )
    (comp (ref "R105")
      (value "4.99")
      (footprint "eagle-import:1206_IPC-7351B")
      (libsource (lib "eagle-import") (part "R901206_IPCGEN"))
    )
    (comp (ref "R106")
      (value "220")
      (footprint "eagle-import:1206_IPC-7351B")
      (libsource (lib "eagle-import") (part "R1206_IPCGEN"))
    )
    (comp (ref "R107")
      (value "220")
      (footprint "eagle-import:1206_IPC-7351B")
      (libsource (lib "eagle-import") (part "R1206_IPCGEN"))
    )
    (comp (ref "R108")
      (value "100")
      (footprint "eagle-import:0805_IPC-7351B")
      (libsource (lib "eagle-import") (part "R0805_IPCGEN"))
    )
    (comp (ref "R109")
      (value "100")
      (footprint "eagle-import:1206_IPC-7351B")
      (libsource (lib "eagle-import") (part "R1206_IPCGEN"))
    )
    (comp (ref "R110")
      (value "100")
      (footprint "eagle-import:0805_IPC-7351B")
      (libsource (lib "eagle-import") (part "R0805_IPCGEN"))
    )
    (comp (ref "R111")
      (value "100")
      (footprint "eagle-import:1206_IPC-7351B")
      (libsource (lib "eagle-import") (part "R1206_IPCGEN"))
    )
    (comp (ref "R112")
      (value "DNP")
      (footprint "eagle-import:0805_IPC-7351B")
      (fields (field (name "BOM") "EXCLUDE"))
      (libsource (lib "eagle-import") (part "R0805_IPCGEN"))
    )
    (comp (ref "R113")
      (value "DNP")
      (footprint "eagle-import:0805_IPC-7351B")
      (fields (field (name "BOM") "EXCLUDE"))
      (libsource (lib "eagle-import") (part "R0805_IPCGEN"))
    )
    (comp (ref "R114")
      (value "15")
      (footprint "eagle-import:0805_IPC-7351B")
      (libsource (lib "eagle-import") (part "R900805_IPCGEN"))
    )
    (comp (ref "R115")
      (value "15")
      (footprint "eagle-import:0805_IPC-7351B")
      (libsource (lib "eagle-import") (part "R900805_IPCGEN"))
    )
    (comp (ref "R116")
      (value "DNP")
      (footprint "eagle-import:0805_IPC-7351B")
      (fields (field (name "BOM") "EXCLUDE"))
      (libsource (lib "eagle-import") (part "R0805_IPCGEN"))
    )
    (comp (ref "R117")
      (value "DNP")
      (footprint "eagle-import:0805_IPC-7351B")
      (fields (field (name "BOM") "EXCLUDE"))
      (libsource (lib "eagle-import") (part "R0805_IPCGEN"))
    )
    (comp (ref "R118")
      (value "2.74K")
      (footprint "eagle-import:R2512")
      (libsource (lib "eagle-import") (part "R90R2512GEN"))
    )
    (comp (ref "R119")
      (value "270")
      (footprint "eagle-import:R2512")
      (libsource (lib "eagle-import") (part "R90R2512GEN"))
    )
    (comp (ref "R120")
      (value "2.74K")
      (footprint "eagle-import:R2512")
      (libsource (lib "eagle-import") (part "R90R2512GEN"))
    )
    (comp (ref "R121")
      (value "270")
      (footprint "eagle-import:R2512")
      (libsource (lib "eagle-import") (part "R90R2512GEN"))
    )
    (comp (ref "R122")
      (value "6.8")
      (footprint "eagle-import:R2512")
      (libsource (lib "eagle-import") (part "RR2512GEN"))
    )
    (comp (ref "R123")
      (value "6.8")
      (footprint "eagle-import:R2512")
      (libsource (lib "eagle-import") (part "RR2512GEN"))
    )
    (comp (ref "R124")
      (value "6.8")
      (footprint "eagle-import:R2512")
      (libsource (lib "eagle-import") (part "RR2512GEN"))
    )
    (comp (ref "R125")
      (value "6.8")
      (footprint "eagle-import:R2512")
      (libsource (lib "eagle-import") (part "RR2512GEN"))
    )
    (comp (ref "R126")
      (value "8.2")
      (footprint "eagle-import:R2512")
      (libsource (lib "eagle-import") (part "RR2512GEN"))
    )
    (comp (ref "R127")
      (value "8.2")
      (footprint "eagle-import:R2512")
      (libsource (lib "eagle-import") (part "RR2512GEN"))
    )
    (comp (ref "R128")
      (value "8.2")
      (footprint "eagle-import:R2512")
      (libsource (lib "eagle-import") (part "RR2512GEN"))
    )
    (comp (ref "R129")
      (value "8.2")
      (footprint "eagle-import:R2512")
      (libsource (lib "eagle-import") (part "RR2512GEN"))
    )
    (comp (ref "R130")
      (value "1K")
      (footprint "eagle-import:0805_IPC-7351B")
      (libsource (lib "eagle-import") (part "R900805_IPCGEN"))
    )
    (comp (ref "R131")
      (value "1K")
      (footprint "eagle-import:0805_IPC-7351B")
      (libsource (lib "eagle-import") (part "R900805_IPCGEN"))
    )
    (comp (ref "R132")
      (value "0")
      (footprint "eagle-import:0805_IPC-7351B")
      (libsource (lib "eagle-import") (part "R0805_IPCGEN"))
    )
    (comp (ref "T101")
      (value "HP4_TRAFO")
      (footprint "eagle-import:HP4")
      (fields (field (name "PARTNO") "HP4-0140LB"))
      (libsource (lib "eagle-import") (part "HP4_TRAFO"))
    )
    (comp (ref "T102")
      (value "HP4_TRAFO")
      (footprint "eagle-import:HP4")
      (fields (field (name "PARTNO") "HP4-0140LB"))
      (libsource (lib "eagle-import") (part "HP4_TRAFO"))
    )
    (comp (ref "TP1")
      (value "PROBE_TPTP_5MM")
      (footprint "eagle-import:PROBE_TP_5MM")
      (libsource (lib "eagle-import") (part "PROBE_TPTP_5MM"))
    )
    (comp (ref "TP2")
      (value "PROBE_TPTP_7P5MM")
      (footprint "eagle-import:PROBE_TP_7P5MM")
      (libsource (lib "eagle-import") (part "PROBE_TPTP_7P5MM"))
    )
    (comp (ref "TP3")
      (value "PROBE_TPTP_5MM")
      (footprint "eagle-import:PROBE_TP_5MM")
      (libsource (lib "eagle-import") (part "PROBE_TPTP_5MM"))
    )
    (comp (ref "TP4")
      (value "PROBE_TPTP_7P5MM")
      (footprint "eagle-import:PROBE_TP_7P5MM")
      (libsource (lib "eagle-import") (part "PROBE_TPTP_7P5MM"))
    )
    (comp (ref "TP5")
      (value "PROBE_TPTP_7P5MM")
      (footprint "eagle-import:PROBE_TP_7P5MM")
      (libsource (lib "eagle-import") (part "PROBE_TPTP_7P5MM"))
    )
    (comp (ref "TP6")
      (value "PROBE_TPTP_7P5MM")
      (footprint "eagle-import:PROBE_TP_7P5MM")
      (libsource (lib "eagle-import") (part "PROBE_TPTP_7P5MM"))
    )
    (comp (ref "TP14")
      (value "PROBE_TPTP_5MM")
      (footprint "eagle-import:PROBE_TP_5MM")
      (libsource (lib "eagle-import") (part "PROBE_TPTP_5MM"))
    )
    (comp (ref "TP15")
      (value "PROBE_TPTP_5MM")
      (footprint "eagle-import:PROBE_TP_5MM")
      (libsource (lib "eagle-import") (part "PROBE_TPTP_5MM"))
    )
    (comp (ref "TP18")
      (value "PROBE_TPTP_5MM")
      (footprint "eagle-import:PROBE_TP_5MM")
      (libsource (lib "eagle-import") (part "PROBE_TPTP_5MM"))
    )
    (comp (ref "TP19")
      (value "PROBE_TPTP_5MM")
      (footprint "eagle-import:PROBE_TP_5MM")
      (libsource (lib "eagle-import") (part "PROBE_TPTP_5MM"))
    )
  )
  (nets
    (net (code "1") (name "+5V") (class "Default")
      (node (ref "C306") (pin "1") (pinfunction "1_1") (pintype "passive"))
      (node (ref "C407") (pin "1") (pinfunction "1_1") (pintype "passive"))
      (node (ref "C410") (pin "+") (pinfunction "+_+") (pintype "passive"))
      (node (ref "LED301") (pin "A") (pinfunction "A_A") (pintype "passive"))
      (node (ref "LED402") (pin "A") (pinfunction "A_A") (pintype "passive"))
      (node (ref "R301") (pin "3") (pinfunction "E_3") (pintype "passive"))
      (node (ref "R408") (pin "1") (pinfunction "1_1") (pintype "passive"))
      (node (ref "U301") (pin "5") (pinfunction "VCC_5") (pintype "power_in"))
      (node (ref "U402") (pin "3") (pinfunction "OUT_3") (pintype "passive"))
    )
    (net (code "2") (name "ABN1") (class "Default")
      (node (ref "R103") (pin "1") (pinfunction "1_1") (pintype "passive"))
      (node (ref "R105") (pin "1") (pinfunction "1_1") (pintype "passive"))
      (node (ref "R202") (pin "1") (pinfunction "1_1") (pintype "passive"))
      (node (ref "R204") (pin "1") (pinfunction "1_1") (pintype "passive"))
      (node (ref "T101") (pin "11") (pinfunction "F2_11") (pintype "passive"))
      (node (ref "TP18") (pin "TP") (pinfunction "1_TP") (pintype "passive"))
    )
    (net (code "3") (name "ABP1") (class "Default")
      (node (ref "R102") (pin "1") (pinfunction "1_1") (pintype "passive"))
      (node (ref "R104") (pin "1") (pinfunction "1_1") (pintype "passive"))
      (node (ref "R201") (pin "1") (pinfunction "1_1") (pintype "passive"))
      (node (ref "R203") (pin "1") (pinfunction "1_1") (pintype "passive"))
      (node (ref "T101") (pin "1") (pinfunction "S1_1") (pintype "passive"))
      (node (ref "TP19") (pin "TP") (pinfunction "1_TP") (pintype "passive"))
    )
    (net (code "4") (name "AN2") (class "Default")
      (node (ref "C107") (pin "2") (pinfunction "2_2") (pintype "passive"))
      (node (ref "R105") (pin "2") (pinfunction "2_2") (pintype "passive"))
      (node (ref "R107") (pin "1") (pinfunction "1_1") (pintype "passive"))
    )
    (net (code "5") (name "AN3") (class "Default")
      (node (ref "C107") (pin "1") (pinfunction "1_1") (pintype "passive"))
      (node (ref "L102") (pin "1") (pinfunction "1_1") (pintype "passive"))
      (node (ref "R111") (pin "2") (pinfunction "2_2") (pintype "passive"))
      (node (ref "R113") (pin "1") (pinfunction "1_1") (pintype "passive"))
      (node (ref "R115") (pin "1") (pinfunction "1_1") (pintype "passive"))
    )
    (net (code "6") (name "AN4") (class "Default")
      (node (ref "L102") (pin "2") (pinfunction "2_2") (pintype "passive"))
      (node (ref "Q102") (pin "G") (pinfunction "G_G") (pintype "passive"))
      (node (ref "R115") (pin "2") (pinfunction "2_2") (pintype "passive"))
      (node (ref "R117") (pin "1") (pinfunction "1_1") (pintype "passive"))
      (node (ref "R120") (pin "1") (pinfunction "1_1") (pintype "passive"))
      (node (ref "R121") (pin "1") (pinfunction "1_1") (pintype "passive"))
      (node (ref "TP3") (pin "TP") (pinfunction "1_TP") (pintype "passive"))
    )
    (net (code "7") (name "AN5") (class "Default")
      (node (ref "Q102") (pin "S") (pinfunction "S_S") (pintype "passive"))
      (node (ref "R123") (pin "1") (pinfunction "1_1") (pintype "passive"))
      (node (ref "R125") (pin "1") (pinfunction "1_1") (pintype "passive"))
      (node (ref "R127") (pin "1") (pinfunction "1_1") (pintype "passive"))
      (node (ref "R129") (pin "1") (pinfunction "1_1") (pintype "passive"))
      (node (ref "R131") (pin "1") (pinfunction "1_1") (pintype "passive"))
      (node (ref "TP6") (pin "TP") (pinfunction "1_TP") (pintype "passive"))
    )
    (net (code "8") (name "AN6") (class "Default")
      (node (ref "C115") (pin "1") (pinfunction "1_1") (pintype "passive"))
      (node (ref "R131") (pin "2") (pinfunction "2_2") (pintype "passive"))
      (node (ref "TP15") (pin "TP") (pinfunction "1_TP") (pintype "passive"))
    )
    (net (code "9") (name "AP2") (class "Default")
      (node (ref "C105") (pin "2") (pinfunction "2_2") (pintype "passive"))
      (node (ref "R104") (pin "2") (pinfunction "2_2") (pintype "passive"))
      (node (ref "R106") (pin "1") (pinfunction "1_1") (pintype "passive"))
    )
    (net (code "10") (name "AP3") (class "Default")
      (node (ref "C105") (pin "1") (pinfunction "1_1") (pintype "passive"))
      (node (ref "L101") (pin "1") (pinfunction "1_1") (pintype "passive"))
      (node (ref "R109") (pin "2") (pinfunction "2_2") (pintype "passive"))
      (node (ref "R112") (pin "1") (pinfunction "1_1") (pintype "passive"))
      (node (ref "R114") (pin "1") (pinfunction "1_1") (pintype "passive"))
    )
    (net (code "11") (name "AP4") (class "Default")
      (node (ref "L101") (pin "2") (pinfunction "2_2") (pintype "passive"))
      (node (ref "Q101") (pin "G") (pinfunction "G_G") (pintype "passive"))
      (node (ref "R114") (pin "2") (pinfunction "2_2") (pintype "passive"))
      (node (ref "R116") (pin "1") (pinfunction "1_1") (pintype "passive"))
      (node (ref "R118") (pin "1") (pinfunction "1_1") (pintype "passive"))
      (node (ref "R119") (pin "1") (pinfunction "1_1") (pintype "passive"))
      (node (ref "TP1") (pin "TP") (pinfunction "1_TP") (pintype "passive"))
    )
    (net (code "12") (name "AP5") (class "Default")
      (node (ref "Q101") (pin "S") (pinfunction "S_S") (pintype "passive"))
      (node (ref "R122") (pin "1") (pinfunction "1_1") (pintype "passive"))
      (node (ref "R124") (pin "1") (pinfunction "1_1") (pintype "passive"))
      (node (ref "R126") (pin "1") (pinfunction "1_1") (pintype "passive"))
      (node (ref "R128") (pin "1") (pinfunction "1_1") (pintype "passive"))
      (node (ref "R130") (pin "1") (pinfunction "1_1") (pintype "passive"))
      (node (ref "TP5") (pin "TP") (pinfunction "1_TP") (pintype "passive"))
    )
    (net (code "13") (name "AP6") (class "Default")
      (node (ref "C114") (pin "1") (pinfunction "1_1") (pintype "passive"))
      (node (ref "R130") (pin "2") (pinfunction "2_2") (pintype "passive"))
      (node (ref "TP14") (pin "TP") (pinfunction "1_TP") (pintype "passive"))
    )
    (net (code "14") (name "BN2") (class "Default")
      (node (ref "C204") (pin "2") (pinfunction "2_2") (pintype "passive"))
      (node (ref "R204") (pin "2") (pinfunction "2_2") (pintype "passive"))
      (node (ref "R206") (pin "1") (pinfunction "1_1") (pintype "passive"))
    )
    (net (code "15") (name "BN3") (class "Default")
      (node (ref "C204") (pin "1") (pinfunction "1_1") (pintype "passive"))
      (node (ref "L202") (pin "1") (pinfunction "1_1") (pintype "passive"))
      (node (ref "R210") (pin "2") (pinfunction "2_2") (pintype "passive"))
      (node (ref "R212") (pin "1") (pinfunction "1_1") (pintype "passive"))
      (node (ref "R214") (pin "1") (pinfunction "1_1") (pintype "passive"))
    )
    (net (code "16") (name "BN4") (class "Default")
      (node (ref "L202") (pin "2") (pinfunction "2_2") (pintype "passive"))
      (node (ref "Q202") (pin "G") (pinfunction "G_G") (pintype "passive"))
      (node (ref "R214") (pin "2") (pinfunction "2_2") (pintype "passive"))
      (node (ref "R216") (pin "1") (pinfunction "1_1") (pintype "passive"))
      (node (ref "R219") (pin "1") (pinfunction "1_1") (pintype "passive"))
      (node (ref "R220") (pin "1") (pinfunction "1_1") (pintype "passive"))
      (node (ref "TP9") (pin "TP") (pinfunction "1_TP") (pintype "passive"))
    )
    (net (code "17") (name "BN5") (class "Default")
      (node (ref "Q202") (pin "S") (pinfunction "S_S") (pintype "passive"))
      (node (ref "R222") (pin "1") (pinfunction "1_1") (pintype "passive"))
      (node (ref "R224") (pin "1") (pinfunction "1_1") (pintype "passive"))
      (node (ref "R226") (pin "1") (pinfunction "1_1") (pintype "passive"))
      (node (ref "R228") (pin "1") (pinfunction "1_1") (pintype "passive"))
      (node (ref "R230") (pin "1") (pinfunction "1_1") (pintype "passive"))
      (node (ref "TP10") (pin "TP") (pinfunction "1_TP") (pintype "passive"))
    )
    (net (code "18") (name "BN6") (class "Default")
      (node (ref "C212") (pin "1") (pinfunction "1_1") (pintype "passive"))
      (node (ref "R230") (pin "2") (pinfunction "2_2") (pintype "passive"))
      (node (ref "TP17") (pin "TP") (pinfunction "1_TP") (pintype "passive"))
    )
    (net (code "19") (name "BP2") (class "Default")
      (node (ref "C202") (pin "2") (pinfunction "2_2") (pintype "passive"))
      (node (ref "R203") (pin "2") (pinfunction "2_2") (pintype "passive"))
      (node (ref "R205") (pin "1") (pinfunction "1_1") (pintype "passive"))
    )
    (net (code "20") (name "BP3") (class "Default")
      (node (ref "C202") (pin "1") (pinfunction "1_1") (pintype "passive"))
      (node (ref "L201") (pin "1") (pinfunction "1_1") (pintype "passive"))
      (node (ref "R208") (pin "2") (pinfunction "2_2") (pintype "passive"))
      (node (ref "R211") (pin "1") (pinfunction "1_1") (pintype "passive"))
      (node (ref "R213") (pin "1") (pinfunction "1_1") (pintype "passive"))
    )
    (net (code "21") (name "BP4") (class "Default")
      (node (ref "L201") (pin "2") (pinfunction "2_2") (pintype "passive"))
      (node (ref "Q201") (pin "G") (pinfunction "G_G") (pintype "passive"))
      (node (ref "R213") (pin "2") (pinfunction "2_2") (pintype "passive"))
      (node (ref "R215") (pin "1") (pinfunction "1_1") (pintype "passive"))
      (node (ref "R217") (pin "1") (pinfunction "1_1") (pintype "passive"))
      (node (ref "R218") (pin "1") (pinfunction "1_1") (pintype "passive"))
      (node (ref "TP7") (pin "TP") (pinfunction "1_TP") (pintype "passive"))
    )
    (net (code "22") (name "BP5") (class "Default")
      (node (ref "Q201") (pin "S") (pinfunction "S_S") (pintype "passive"))
      (node (ref "R221") (pin "1") (pinfunction "1_1") (pintype "passive"))
      (node (ref "R223") (pin "1") (pinfunction "1_1") (pintype "passive"))
      (node (ref "R225") (pin "1") (pinfunction "1_1") (pintype "passive"))
      (node (ref "R227") (pin "1") (pinfunction "1_1") (pintype "passive"))
      (node (ref "R229") (pin "1") (pinfunction "1_1") (pintype "passive"))
      (node (ref "TP8") (pin "TP") (pinfunction "1_TP") (pintype "passive"))
    )
    (net (code "23") (name "BP6") (class "Default")
      (node (ref "C211") (pin "1") (pinfunction "1_1") (pintype "passive"))
      (node (ref "R229") (pin "2") (pinfunction "2_2") (pintype "passive"))
      (node (ref "TP16") (pin "TP") (pinfunction "1_TP") (pintype "passive"))
    )
    (net (code "24") (name "DRAINS_NEG") (class "Default")
      (node (ref "C113") (pin "2") (pinfunction "2_2") (pintype "passive"))
      (node (ref "C117") (pin "2") (pinfunction "2_2") (pintype "passive"))
      (node (ref "C210") (pin "2") (pinfunction "2_2") (pintype "passive"))
      (node (ref "L104") (pin "1") (pinfunction "1_1") (pintype "passive"))
      (node (ref "Q102") (pin "D") (pinfunction "D_D") (pintype "passive"))
      (node (ref "Q202") (pin "D") (pinfunction "D_D") (pintype "passive"))
      (node (ref "T102") (pin "8") (pinfunction "F5_8") (pintype "passive"))
      (node (ref "TP4") (pin "TP") (pinfunction "1_TP") (pintype "passive"))
    )
    (net (code "25") (name "DRAINS_POS") (class "Default")
      (node (ref "C112") (pin "2") (pinfunction "2_2") (pintype "passive"))
      (node (ref "C116") (pin "2") (pinfunction "2_2") (pintype "passive"))
      (node (ref "C209") (pin "2") (pinfunction "2_2") (pintype "passive"))
      (node (ref "L103") (pin "1") (pinfunction "1_1") (pintype "passive"))
      (node (ref "Q101") (pin "D") (pinfunction "D_D") (pintype "passive"))
      (node (ref "Q201") (pin "D") (pinfunction "D_D") (pintype "passive"))
      (node (ref "T102") (pin "6") (pinfunction "S6_6") (pintype "passive"))
      (node (ref "TP2") (pin "TP") (pinfunction "1_TP") (pintype "passive"))
    )
    (net (code "26") (name "GBIAS") (class "Default")
      (node (ref "Q302") (pin "2") (pinfunction "E_2") (pintype "passive"))
      (node (ref "Q303") (pin "2") (pinfunction "E_2") (pintype "passive"))
      (node (ref "R108") (pin "1") (pinfunction "1_1") (pintype "passive"))
      (node (ref "R110") (pin "1") (pinfunction "1_1") (pintype "passive"))
      (node (ref "R207") (pin "1") (pinfunction "1_1") (pintype "passive"))
      (node (ref "R209") (pin "1") (pinfunction "1_1") (pintype "passive"))
      (node (ref "R316") (pin "2") (pinfunction "2_2") (pintype "passive"))
      (node (ref "R317") (pin "2") (pinfunction "2_2") (pintype "passive"))
      (node (ref "TP11") (pin "TP") (pinfunction "1_TP") (pintype "passive"))
    )
    (net (code "27") (name "Net-(C104-Pad1)") (class "Default")
      (node (ref "C104") (pin "1") (pinfunction "1_1") (pintype "passive"))
      (node (ref "R108") (pin "2") (pinfunction "2_2") (pintype "passive"))
      (node (ref "R109") (pin "1") (pinfunction "1_1") (pintype "passive"))
    )
    (net (code "28") (name "Net-(C106-Pad1)") (class "Default")
      (node (ref "C106") (pin "1") (pinfunction "1_1") (pintype "passive"))
      (node (ref "R110") (pin "2") (pinfunction "2_2") (pintype "passive"))
      (node (ref "R111") (pin "1") (pinfunction "1_1") (pintype "passive"))
    )
    (net (code "29") (name "Net-(C108-Pad1)") (class "Default")
      (node (ref "C108") (pin "1") (pinfunction "1_1") (pintype "passive"))
      (node (ref "R112") (pin "2") (pinfunction "2_2") (pintype "passive"))
    )
    (net (code "30") (name "Net-(C109-Pad1)") (class "Default")
      (node (ref "C109") (pin "1") (pinfunction "1_1") (pintype "passive"))
      (node (ref "R113") (pin "2") (pinfunction "2_2") (pintype "passive"))
    )
    (net (code "31") (name "Net-(C110-Pad1)") (class "Default")
      (node (ref "C110") (pin "1") (pinfunction "1_1") (pintype "passive"))
      (node (ref "R116") (pin "2") (pinfunction "2_2") (pintype "passive"))
    )
    (net (code "32") (name "Net-(C111-Pad1)") (class "Default")
      (node (ref "C111") (pin "1") (pinfunction "1_1") (pintype "passive"))
      (node (ref "R117") (pin "2") (pinfunction "2_2") (pintype "passive"))
    )
    (net (code "33") (name "Net-(C112-Pad1)") (class "Default")
      (node (ref "C112") (pin "1") (pinfunction "1_1") (pintype "passive"))
      (node (ref "R118") (pin "2") (pinfunction "2_2") (pintype "passive"))
      (node (ref "R119") (pin "2") (pinfunction "2_2") (pintype "passive"))
    )
    (net (code "34") (name "Net-(C113-Pad1)") (class "Default")
      (node (ref "C113") (pin "1") (pinfunction "1_1") (pintype "passive"))
      (node (ref "R120") (pin "2") (pinfunction "2_2") (pintype "passive"))
      (node (ref "R121") (pin "2") (pinfunction "2_2") (pintype "passive"))
    )
    (net (code "35") (name "Net-(C201-Pad1)") (class "Default")
      (node (ref "C201") (pin "1") (pinfunction "1_1") (pintype "passive"))
      (node (ref "R207") (pin "2") (pinfunction "2_2") (pintype "passive"))
      (node (ref "R208") (pin "1") (pinfunction "1_1") (pintype "passive"))
    )
    (net (code "36") (name "Net-(C203-Pad1)") (class "Default")
      (node (ref "C203") (pin "1") (pinfunction "1_1") (pintype "passive"))
      (node (ref "R209") (pin "2") (pinfunction "2_2") (pintype "passive"))
      (node (ref "R210") (pin "1") (pinfunction "1_1") (pintype "passive"))
    )
    (net (code "37") (name "Net-(C205-Pad1)") (class "Default")
      (node (ref "C205") (pin "1") (pinfunction "1_1") (pintype "passive"))
      (node (ref "R211") (pin "2") (pinfunction "2_2") (pintype "passive"))
    )
    (net (code "38") (name "Net-(C206-Pad1)") (class "Default")
      (node (ref "C206") (pin "1") (pinfunction "1_1") (pintype "passive"))
      (node (ref "R212") (pin "2") (pinfunction "2_2") (pintype "passive"))
    )
    (net (code "39") (name "Net-(C207-Pad1)") (class "Default")
      (node (ref "C207") (pin "1") (pinfunction "1_1") (pintype "passive"))
      (node (ref "R215") (pin "2") (pinfunction "2_2") (pintype "passive"))
    )
    (net (code "40") (name "Net-(C208-Pad1)") (class "Default")
      (node (ref "C208") (pin "1") (pinfunction "1_1") (pintype "passive"))
      (node (ref "R216") (pin "2") (pinfunction "2_2") (pintype "passive"))
    )
    (net (code "41") (name "Net-(C209-Pad1)") (class "Default")
      (node (ref "C209") (pin "1") (pinfunction "1_1") (pintype "passive"))
      (node (ref "R217") (pin "2") (pinfunction "2_2") (pintype "passive"))
      (node (ref "R218") (pin "2") (pinfunction "2_2") (pintype "passive"))
    )
    (net (code "42") (name "Net-(C210-Pad1)") (class "Default")
      (node (ref "C210") (pin "1") (pinfunction "1_1") (pintype "passive"))
      (node (ref "R219") (pin "2") (pinfunction "2_2") (pintype "passive"))
      (node (ref "R220") (pin "2") (pinfunction "2_2") (pintype "passive"))
    )
    (net (code "43") (name "Net-(C302-Pad1)") (class "Default")
      (node (ref "C302") (pin "1") (pinfunction "1_1") (pintype "passive"))
      (node (ref "R313") (pin "1") (pinfunction "1_1") (pintype "passive"))
    )
    (net (code "44") (name "Net-(C304-Pad1)") (class "Default")
      (node (ref "C304") (pin "1") (pinfunction "1_1") (pintype "passive"))
      (node (ref "R314") (pin "2") (pinfunction "2_2") (pintype "passive"))
    )
    (net (code "45") (name "Net-(C405-Pad1)") (class "Default")
      (node (ref "C405") (pin "1") (pinfunction "1_1") (pintype "passive"))
      (node (ref "L401") (pin "2") (pinfunction "2_2") (pintype "passive"))
      (node (ref "L402") (pin "1") (pinfunction "1_1") (pintype "passive"))
      (node (ref "R404") (pin "1") (pinfunction "1_1") (pintype "passive"))
      (node (ref "R405") (pin "1") (pinfunction "1_1") (pintype "passive"))
    )
    (net (code "46") (name "Net-(D401-C1)") (class "Default")
      (node (ref "D401") (pin "K") (pinfunction "C1_K") (pintype "passive"))
      (node (ref "F401") (pin "2") (pinfunction "2_2") (pintype "passive"))
      (node (ref "R401") (pin "1") (pinfunction "1_1") (pintype "passive"))
    )
    (net (code "47") (name "Net-(D402-A1)") (class "Default")
      (node (ref "D402") (pin "A") (pinfunction "A1_A") (pintype "passive"))
      (node (ref "R402") (pin "1") (pinfunction "1_1") (pintype "passive"))
      (node (ref "R403") (pin "1") (pinfunction "1_1") (pintype "passive"))
    )
    (net (code "48") (name "Net-(D402-C1)") (class "Default")
      (node (ref "C401") (pin "+") (pinfunction "+_+") (pintype "passive"))
      (node (ref "C402") (pin "1") (pinfunction "1_1") (pintype "passive"))
      (node (ref "D402") (pin "C") (pinfunction "C1_C") (pintype "passive"))
      (node (ref "L401") (pin "1") (pinfunction "1_1") (pintype "passive"))
      (node (ref "R401") (pin "2") (pinfunction "2_2") (pintype "passive"))
    )
    (net (code "49") (name "Net-(F401-Pad1)") (class "Default")
      (node (ref "F401") (pin "1") (pinfunction "1_1") (pintype "passive"))
      (node (ref "J401") (pin "1") (pinfunction "1_1") (pintype "passive"))
    )
    (net (code "50") (name "Net-(J101-1)") (class "Default")
      (node (ref "C101") (pin "2") (pinfunction "2_2") (pintype "passive"))
      (node (ref "C102") (pin "2") (pinfunction "2_2") (pintype "passive"))
      (node (ref "C103") (pin "2") (pinfunction "2_2") (pintype "passive"))
      (node (ref "J101") (pin "C") (pinfunction "1_C") (pintype "passive"))
    )
    (net (code "51") (name "Net-(J102-1)") (class "Default")
      (node (ref "C118") (pin "2") (pinfunction "2_2") (pintype "passive"))
      (node (ref "C119") (pin "2") (pinfunction "2_2") (pintype "passive"))
      (node (ref "C120") (pin "2") (pinfunction "2_2") (pintype "passive"))
      (node (ref "J102") (pin "C") (pinfunction "1_C") (pintype "passive"))
    )
    (net (code "52") (name "Net-(J301-1)") (class "Default")
      (node (ref "J301") (pin "C") (pinfunction "1_C") (pintype "passive"))
      (node (ref "JP301") (pin "2") (pinfunction "2_2") (pintype "passive"))
      (node (ref "R302") (pin "1") (pinfunction "1_1") (pintype "passive"))
    )
    (net (code "53") (name "Net-(J301-GND1-PadG1)") (class "Default")
      (node (ref "J301") (pin "G1") (pinfunction "GND1_G1") (pintype "power_in"))
      (node (ref "J301") (pin "G2") (pinfunction "GND1_G2") (pintype "power_in"))
      (node (ref "J301") (pin "G3") (pinfunction "GND1_G3") (pintype "power_in"))
      (node (ref "J301") (pin "G4") (pinfunction "GND1_G4") (pintype "power_in"))
      (node (ref "JP301") (pin "1") (pinfunction "1_1") (pintype "passive"))
      (node (ref "R303") (pin "1") (pinfunction "1_1") (pintype "passive"))
    )
    (net (code "54") (name "Net-(J302-1)") (class "Default")
      (node (ref "J302") (pin "C") (pinfunction "1_C") (pintype "passive"))
      (node (ref "R304") (pin "1") (pinfunction "1_1") (pintype "passive"))
    )
    (net (code "55") (name "Net-(J402-Pad3)") (class "Default")
      (node (ref "J402") (pin "3") (pinfunction "3_3") (pintype "passive"))
      (node (ref "R408") (pin "2") (pinfunction "2_2") (pintype "passive"))
    )
    (net (code "56") (name "Net-(LED301-C)") (class "Default")
      (node (ref "LED301") (pin "K") (pinfunction "C_K") (pintype "passive"))
      (node (ref "R309") (pin "1") (pinfunction "1_1") (pintype "passive"))
    )
    (net (code "57") (name "Net-(LED401-C)") (class "Default")
      (node (ref "LED401") (pin "K") (pinfunction "C_K") (pintype "passive"))
      (node (ref "R406") (pin "1") (pinfunction "1_1") (pintype "passive"))
    )
    (net (code "58") (name "Net-(LED402-C)") (class "Default")
      (node (ref "LED402") (pin "K") (pinfunction "C_K") (pintype "passive"))
      (node (ref "R407") (pin "1") (pinfunction "1_1") (pintype "passive"))
    )
    (net (code "59") (name "Net-(Q301-D)") (class "Default")
      (node (ref "Q301") (pin "3") (pinfunction "D_3") (pintype "passive"))
      (node (ref "R308") (pin "2") (pinfunction "2_2") (pintype "passive"))
      (node (ref "U302") (pin "5") (pinfunction "+IN_5") (pintype "input"))
    )
    (net (code "60") (name "Net-(Q301-G)") (class "Default")
      (node (ref "Q301") (pin "1") (pinfunction "G_1") (pintype "passive"))
      (node (ref "R309") (pin "2") (pinfunction "2_2") (pintype "passive"))
      (node (ref "U301") (pin "4") (pinfunction "O_4") (pintype "output"))
    )
    (net (code "61") (name "Net-(Q302-B)") (class "Default")
      (node (ref "Q302") (pin "1") (pinfunction "B_1") (pintype "passive"))
      (node (ref "Q303") (pin "1") (pinfunction "B_1") (pintype "passive"))
      (node (ref "R315") (pin "2") (pinfunction "2_2") (pintype "passive"))
      (node (ref "R316") (pin "1") (pinfunction "1_1") (pintype "passive"))
    )
    (net (code "62") (name "Net-(R301-S)") (class "Default")
      (node (ref "C301") (pin "1") (pinfunction "1_1") (pintype "passive"))
      (node (ref "R301") (pin "2") (pinfunction "S_2") (pintype "passive"))
      (node (ref "U302") (pin "12") (pinfunction "+IN_12") (pintype "input"))
    )
    (net (code "63") (name "Net-(T101-F1)") (class "Default")
      (node (ref "R101") (pin "1") (pinfunction "1_1") (pintype "passive"))
      (node (ref "T101") (pin "12") (pinfunction "F1_12") (pintype "passive"))
      (node (ref "T101") (pin "2") (pinfunction "S2_2") (pintype "passive"))
    )
    (net (code "64") (name "Net-(T101-F4)") (class "Default")
      (node (ref "T101") (pin "3") (pinfunction "S3_3") (pintype "passive"))
      (node (ref "T101") (pin "9") (pinfunction "F4_9") (pintype "passive"))
    )
    (net (code "65") (name "Net-(T101-F5)") (class "Default")
      (node (ref "C101") (pin "1") (pinfunction "1_1") (pintype "passive"))
      (node (ref "T101") (pin "4") (pinfunction "S4_4") (pintype "passive"))
      (node (ref "T101") (pin "8") (pinfunction "F5_8") (pintype "passive"))
    )
    (net (code "66") (name "Net-(T101-F6)") (class "Default")
      (node (ref "C102") (pin "1") (pinfunction "1_1") (pintype "passive"))
      (node (ref "T101") (pin "5") (pinfunction "S5_5") (pintype "passive"))
      (node (ref "T101") (pin "7") (pinfunction "F6_7") (pintype "passive"))
    )
    (net (code "67") (name "Net-(T101-S6)") (class "Default")
      (node (ref "C103") (pin "1") (pinfunction "1_1") (pintype "passive"))
      (node (ref "T101") (pin "6") (pinfunction "S6_6") (pintype "passive"))
    )
    (net (code "68") (name "Net-(T102-F1)") (class "Default")
      (node (ref "C119") (pin "1") (pinfunction "1_1") (pintype "passive"))
      (node (ref "T102") (pin "12") (pinfunction "F1_12") (pintype "passive"))
      (node (ref "T102") (pin "2") (pinfunction "S2_2") (pintype "passive"))
    )
    (net (code "69") (name "Net-(T102-F2)") (class "Default")
      (node (ref "C118") (pin "1") (pinfunction "1_1") (pintype "passive"))
      (node (ref "T102") (pin "11") (pinfunction "F2_11") (pintype "passive"))
      (node (ref "T102") (pin "3") (pinfunction "S3_3") (pintype "passive"))
    )
    (net (code "70") (name "Net-(T102-F3)") (class "Default")
      (node (ref "T102") (pin "10") (pinfunction "F3_10") (pintype "passive"))
      (node (ref "T102") (pin "4") (pinfunction "S4_4") (pintype "passive"))
    )
    (net (code "71") (name "Net-(T102-F6)") (class "Default")
      (node (ref "R132") (pin "2") (pinfunction "2_2") (pintype "passive"))
      (node (ref "T102") (pin "5") (pinfunction "S5_5") (pintype "passive"))
      (node (ref "T102") (pin "7") (pinfunction "F6_7") (pintype "passive"))
    )
    (net (code "72") (name "Net-(T102-S1)") (class "Default")
      (node (ref "C120") (pin "1") (pinfunction "1_1") (pintype "passive"))
      (node (ref "T102") (pin "1") (pinfunction "S1_1") (pintype "passive"))
    )
    (net (code "73") (name "Net-(TP12-1)") (class "Default")
      (node (ref "R310") (pin "1") (pinfunction "1_1") (pintype "passive"))
      (node (ref "TP12") (pin "TP") (pinfunction "1_TP") (pintype "passive"))
      (node (ref "U302") (pin "6") (pinfunction "-IN_6") (pintype "input"))
      (node (ref "U302") (pin "7") (pinfunction "OUT_7") (pintype "output"))
    )
    (net (code "74") (name "Net-(TP13-1)") (class "Default")
      (node (ref "R306") (pin "2") (pinfunction "2_2") (pintype "passive"))
      (node (ref "TP13") (pin "TP") (pinfunction "1_TP") (pintype "passive"))
      (node (ref "U302") (pin "13") (pinfunction "-IN_13") (pintype "input"))
      (node (ref "U302") (pin "14") (pinfunction "OUT_14") (pintype "output"))
    )
    (net (code "75") (name "Net-(U301A-I)") (class "Default")
      (node (ref "R304") (pin "2") (pinfunction "2_2") (pintype "passive"))
      (node (ref "R307") (pin "1") (pinfunction "1_1") (pintype "passive"))
      (node (ref "U301") (pin "2") (pinfunction "I_2") (pintype "input"))
    )
    (net (code "76") (name "Net-(U302A-+IN)") (class "Default")
      (node (ref "C303") (pin "1") (pinfunction "1_1") (pintype "passive"))
      (node (ref "R310") (pin "2") (pinfunction "2_2") (pintype "passive"))
      (node (ref "R311") (pin "1") (pinfunction "1_1") (pintype "passive"))
      (node (ref "U302") (pin "3") (pinfunction "+IN_3") (pintype "input"))
    )
    (net (code "77") (name "Net-(U302A--IN)") (class "Default")
      (node (ref "C304") (pin "2") (pinfunction "2_2") (pintype "passive"))
      (node (ref "R312") (pin "2") (pinfunction "2_2") (pintype "passive"))
      (node (ref "R313") (pin "2") (pinfunction "2_2") (pintype "passive"))
      (node (ref "R317") (pin "1") (pinfunction "1_1") (pintype "passive"))
      (node (ref "U302") (pin "2") (pinfunction "-IN_2") (pintype "input"))
    )
    (net (code "78") (name "Net-(U302A-OUT)") (class "Default")
      (node (ref "R314") (pin "1") (pinfunction "1_1") (pintype "passive"))
      (node (ref "R315") (pin "1") (pinfunction "1_1") (pintype "passive"))
      (node (ref "U302") (pin "1") (pinfunction "OUT_1") (pintype "output"))
    )
    (net (code "79") (name "Net-(U302C-+IN)") (class "Default")
      (node (ref "R303") (pin "2") (pinfunction "2_2") (pintype "passive"))
      (node (ref "R306") (pin "1") (pinfunction "1_1") (pintype "passive"))
      (node (ref "U302") (pin "10") (pinfunction "+IN_10") (pintype "input"))
    )
    (net (code "80") (name "Net-(U302C--IN)") (class "Default")
      (node (ref "JP302") (pin "1") (pinfunction "1_1") (pintype "passive"))
      (node (ref "R302") (pin "2") (pinfunction "2_2") (pintype "passive"))
      (node (ref "R305") (pin "1") (pinfunction "1_1") (pintype "passive"))
      (node (ref "U302") (pin "9") (pinfunction "-IN_9") (pintype "input"))
    )
    (net (code "81") (name "Net-(U302C-OUT)") (class "Default")
      (node (ref "JP302") (pin "2") (pinfunction "2_2") (pintype "passive"))
      (node (ref "R305") (pin "2") (pinfunction "2_2") (pintype "passive"))
      (node (ref "R308") (pin "1") (pinfunction "1_1") (pintype "passive"))
      (node (ref "U302") (pin "8") (pinfunction "OUT_8") (pintype "output"))
    )
    (net (code "82") (name "Net-(U401-IN)") (class "Default")
      (node (ref "C403") (pin "1") (pinfunction "1_1") (pintype "passive"))
      (node (ref "R402") (pin "2") (pinfunction "2_2") (pintype "passive"))
      (node (ref "U401") (pin "1") (pinfunction "IN_1") (pintype "input"))
    )
    (net (code "83") (name "Net-(U402-IN)") (class "Default")
      (node (ref "C404") (pin "1") (pinfunction "1_1") (pintype "passive"))
      (node (ref "R403") (pin "2") (pinfunction "2_2") (pintype "passive"))
      (node (ref "U402") (pin "1") (pinfunction "IN_1") (pintype "input"))
    )
    (net (code "84") (name "V+") (class "Default")
      (node (ref "C305") (pin "1") (pinfunction "1_1") (pintype "passive"))
      (node (ref "C406") (pin "1") (pinfunction "1_1") (pintype "passive"))
      (node (ref "C409") (pin "+") (pinfunction "+_+") (pintype "passive"))
      (node (ref "J402") (pin "2") (pinfunction "2_2") (pintype "passive"))
      (node (ref "LED401") (pin "A") (pinfunction "A_A") (pintype "passive"))
      (node (ref "Q303") (pin "3") (pinfunction "C_3") (pintype "passive"))
      (node (ref "U302") (pin "4") (pinfunction "V+_4") (pintype "power_in"))
      (node (ref "U401") (pin "3") (pinfunction "OUT_3") (pintype "passive"))
    )
    (net (code "85") (name "V-") (class "Default")
      (node (ref "C104") (pin "2") (pinfunction "2_2") (pintype "passive"))
      (node (ref "C106") (pin "2") (pinfunction "2_2") (pintype "passive"))
      (node (ref "C108") (pin "2") (pinfunction "2_2") (pintype "passive"))
      (node (ref "C109") (pin "2") (pinfunction "2_2") (pintype "passive"))
      (node (ref "C110") (pin "2") (pinfunction "2_2") (pintype "passive"))
      (node (ref "C111") (pin "2") (pinfunction "2_2") (pintype "passive"))
      (node (ref "C114") (pin "2") (pinfunction "2_2") (pintype "passive"))
      (node (ref "C115") (pin "2") (pinfunction "2_2") (pintype "passive"))
      (node (ref "C201") (pin "2") (pinfunction "2_2") (pintype "passive"))
      (node (ref "C203") (pin "2") (pinfunction "2_2") (pintype "passive"))
      (node (ref "C205") (pin "2") (pinfunction "2_2") (pintype "passive"))
      (node (ref "C206") (pin "2") (pinfunction "2_2") (pintype "passive"))
      (node (ref "C207") (pin "2") (pinfunction "2_2") (pintype "passive"))
      (node (ref "C208") (pin "2") (pinfunction "2_2") (pintype "passive"))
      (node (ref "C211") (pin "2") (pinfunction "2_2") (pintype "passive"))
      (node (ref "C212") (pin "2") (pinfunction "2_2") (pintype "passive"))
      (node (ref "C301") (pin "2") (pinfunction "2_2") (pintype "passive"))
      (node (ref "C302") (pin "2") (pinfunction "2_2") (pintype "passive"))
      (node (ref "C303") (pin "2") (pinfunction "2_2") (pintype "passive"))
      (node (ref "C305") (pin "2") (pinfunction "2_2") (pintype "passive"))
      (node (ref "C306") (pin "2") (pinfunction "2_2") (pintype "passive"))
      (node (ref "C401") (pin "-") (pinfunction "-_-") (pintype "passive"))
      (node (ref "C402") (pin "2") (pinfunction "2_2") (pintype "passive"))
      (node (ref "C403") (pin "2") (pinfunction "2_2") (pintype "passive"))
      (node (ref "C404") (pin "2") (pinfunction "2_2") (pintype "passive"))
      (node (ref "C405") (pin "2") (pinfunction "2_2") (pintype "passive"))
      (node (ref "C406") (pin "2") (pinfunction "2_2") (pintype "passive"))
      (node (ref "C407") (pin "2") (pinfunction "2_2") (pintype "passive"))
      (node (ref "C408") (pin "2") (pinfunction "2_2") (pintype "passive"))
      (node (ref "C409") (pin "-") (pinfunction "-_-") (pintype "passive"))
      (node (ref "C410") (pin "-") (pinfunction "-_-") (pintype "passive"))
      (node (ref "C411") (pin "2") (pinfunction "2_2") (pintype "passive"))
      (node (ref "C412") (pin "2") (pinfunction "2_2") (pintype "passive"))
      (node (ref "C413") (pin "2") (pinfunction "2_2") (pintype "passive"))
      (node (ref "D401") (pin "A") (pinfunction "A1_A") (pintype "passive"))
      (node (ref "H401") (pin "B3,2") (pinfunction "MOUNT_B3,2") (pintype "passive"))
      (node (ref "H402") (pin "B3,2") (pinfunction "MOUNT_B3,2") (pintype "passive"))
      (node (ref "H403") (pin "B3,2") (pinfunction "MOUNT_B3,2") (pintype "passive"))
      (node (ref "H404") (pin "B3,2") (pinfunction "MOUNT_B3,2") (pintype "passive"))
      (node (ref "J101") (pin "G1") (pinfunction "GND1_G1") (pintype "power_in"))
      (node (ref "J101") (pin "G2") (pinfunction "GND1_G2") (pintype "power_in"))
      (node (ref "J101") (pin "G3") (pinfunction "GND1_G3") (pintype "power_in"))
      (node (ref "J101") (pin "G4") (pinfunction "GND1_G4") (pintype "power_in"))
      (node (ref "J102") (pin "G1") (pinfunction "GND1_G1") (pintype "power_in"))
      (node (ref "J102") (pin "G2") (pinfunction "GND1_G2") (pintype "power_in"))
      (node (ref "J102") (pin "G3") (pinfunction "GND1_G3") (pintype "power_in"))
      (node (ref "J102") (pin "G4") (pinfunction "GND1_G4") (pintype "power_in"))
      (node (ref "J302") (pin "G1") (pinfunction "GND1_G1") (pintype "power_in"))
      (node (ref "J302") (pin "G2") (pinfunction "GND1_G2") (pintype "power_in"))
      (node (ref "J302") (pin "G3") (pinfunction "GND1_G3") (pintype "power_in"))
      (node (ref "J302") (pin "G4") (pinfunction "GND1_G4") (pintype "power_in"))
      (node (ref "J401") (pin "2") (pinfunction "2_2") (pintype "passive"))
      (node (ref "J402") (pin "1") (pinfunction "1_1") (pintype "passive"))
      (node (ref "Q301") (pin "2") (pinfunction "S_2") (pintype "passive"))
      (node (ref "Q302") (pin "3") (pinfunction "C_3") (pintype "passive"))
      (node (ref "R101") (pin "2") (pinfunction "2_2") (pintype "passive"))
      (node (ref "R102") (pin "2") (pinfunction "2_2") (pintype "passive"))
      (node (ref "R103") (pin "2") (pinfunction "2_2") (pintype "passive"))
      (node (ref "R106") (pin "2") (pinfunction "2_2") (pintype "passive"))
      (node (ref "R107") (pin "2") (pinfunction "2_2") (pintype "passive"))
      (node (ref "R122") (pin "2") (pinfunction "2_2") (pintype "passive"))
      (node (ref "R123") (pin "2") (pinfunction "2_2") (pintype "passive"))
      (node (ref "R124") (pin "2") (pinfunction "2_2") (pintype "passive"))
      (node (ref "R125") (pin "2") (pinfunction "2_2") (pintype "passive"))
      (node (ref "R126") (pin "2") (pinfunction "2_2") (pintype "passive"))
      (node (ref "R127") (pin "2") (pinfunction "2_2") (pintype "passive"))
      (node (ref "R128") (pin "2") (pinfunction "2_2") (pintype "passive"))
      (node (ref "R129") (pin "2") (pinfunction "2_2") (pintype "passive"))
      (node (ref "R201") (pin "2") (pinfunction "2_2") (pintype "passive"))
      (node (ref "R202") (pin "2") (pinfunction "2_2") (pintype "passive"))
      (node (ref "R205") (pin "2") (pinfunction "2_2") (pintype "passive"))
      (node (ref "R206") (pin "2") (pinfunction "2_2") (pintype "passive"))
      (node (ref "R221") (pin "2") (pinfunction "2_2") (pintype "passive"))
      (node (ref "R222") (pin "2") (pinfunction "2_2") (pintype "passive"))
      (node (ref "R223") (pin "2") (pinfunction "2_2") (pintype "passive"))
      (node (ref "R224") (pin "2") (pinfunction "2_2") (pintype "passive"))
      (node (ref "R225") (pin "2") (pinfunction "2_2") (pintype "passive"))
      (node (ref "R226") (pin "2") (pinfunction "2_2") (pintype "passive"))
      (node (ref "R227") (pin "2") (pinfunction "2_2") (pintype "passive"))
      (node (ref "R228") (pin "2") (pinfunction "2_2") (pintype "passive"))
      (node (ref "R301") (pin "1") (pinfunction "A_1") (pintype "passive"))
      (node (ref "R307") (pin "2") (pinfunction "2_2") (pintype "passive"))
      (node (ref "R311") (pin "2") (pinfunction "2_2") (pintype "passive"))
      (node (ref "R312") (pin "1") (pinfunction "1_1") (pintype "passive"))
      (node (ref "R406") (pin "2") (pinfunction "2_2") (pintype "passive"))
      (node (ref "R407") (pin "2") (pinfunction "2_2") (pintype "passive"))
      (node (ref "T101") (pin "10") (pinfunction "F3_10") (pintype "passive"))
      (node (ref "T102") (pin "9") (pinfunction "F4_9") (pintype "passive"))
      (node (ref "TP1") (pin "GND") (pinfunction "GND1_GND") (pintype "power_in"))
      (node (ref "TP10") (pin "GND") (pinfunction "GND1_GND") (pintype "power_in"))
      (node (ref "TP11") (pin "GND") (pinfunction "GND1_GND") (pintype "power_in"))
      (node (ref "TP12") (pin "GND") (pinfunction "GND1_GND") (pintype "power_in"))
      (node (ref "TP13") (pin "GND") (pinfunction "GND1_GND") (pintype "power_in"))
      (node (ref "TP14") (pin "GND") (pinfunction "GND1_GND") (pintype "power_in"))
      (node (ref "TP15") (pin "GND") (pinfunction "GND1_GND") (pintype "power_in"))
      (node (ref "TP16") (pin "GND") (pinfunction "GND1_GND") (pintype "power_in"))
      (node (ref "TP17") (pin "GND") (pinfunction "GND1_GND") (pintype "power_in"))
      (node (ref "TP18") (pin "GND") (pinfunction "GND1_GND") (pintype "power_in"))
      (node (ref "TP19") (pin "GND") (pinfunction "GND1_GND") (pintype "power_in"))
      (node (ref "TP2") (pin "GND") (pinfunction "GND1_GND") (pintype "power_in"))
      (node (ref "TP3") (pin "GND") (pinfunction "GND1_GND") (pintype "power_in"))
      (node (ref "TP4") (pin "GND") (pinfunction "GND1_GND") (pintype "power_in"))
      (node (ref "TP5") (pin "GND") (pinfunction "GND1_GND") (pintype "power_in"))
      (node (ref "TP6") (pin "GND") (pinfunction "GND1_GND") (pintype "power_in"))
      (node (ref "TP7") (pin "GND") (pinfunction "GND1_GND") (pintype "power_in"))
      (node (ref "TP8") (pin "GND") (pinfunction "GND1_GND") (pintype "power_in"))
      (node (ref "TP9") (pin "GND") (pinfunction "GND1_GND") (pintype "power_in"))
      (node (ref "U301") (pin "3") (pinfunction "GND_3") (pintype "power_in"))
      (node (ref "U302") (pin "11") (pinfunction "V-_11") (pintype "power_in"))
      (node (ref "U401") (pin "2") (pinfunction "GND_2") (pintype "input"))
      (node (ref "U402") (pin "2") (pinfunction "GND_2") (pintype "input"))
      (node (ref "X402") (pin "P1") (pinfunction "P$1_P1") (pintype "bidirectional"))
      (node (ref "X402") (pin "P2") (pinfunction "P$2_P2") (pintype "bidirectional"))
    )
    (net (code "86") (name "VB") (class "Default")
      (node (ref "C116") (pin "1") (pinfunction "1_1") (pintype "passive"))
      (node (ref "C117") (pin "1") (pinfunction "1_1") (pintype "passive"))
      (node (ref "C408") (pin "1") (pinfunction "1_1") (pintype "passive"))
      (node (ref "C411") (pin "1") (pinfunction "1_1") (pintype "passive"))
      (node (ref "C412") (pin "1") (pinfunction "1_1") (pintype "passive"))
      (node (ref "C413") (pin "1") (pinfunction "1_1") (pintype "passive"))
      (node (ref "L103") (pin "2") (pinfunction "2_2") (pintype "passive"))
      (node (ref "L104") (pin "2") (pinfunction "2_2") (pintype "passive"))
      (node (ref "L402") (pin "2") (pinfunction "2_2") (pintype "passive"))
      (node (ref "R132") (pin "1") (pinfunction "1_1") (pintype "passive"))
      (node (ref "R404") (pin "2") (pinfunction "2_2") (pintype "passive"))
      (node (ref "R405") (pin "2") (pinfunction "2_2") (pintype "passive"))
    )
    (net (code "87") (name "unconnected-(J402-Pad4)") (class "Default")
      (node (ref "J402") (pin "4") (pinfunction "4_4") (pintype "passive"))
    )
  )
)
